# vm_mini_main3a.net
KiCad netlist of a schematic drawn in EAGLE
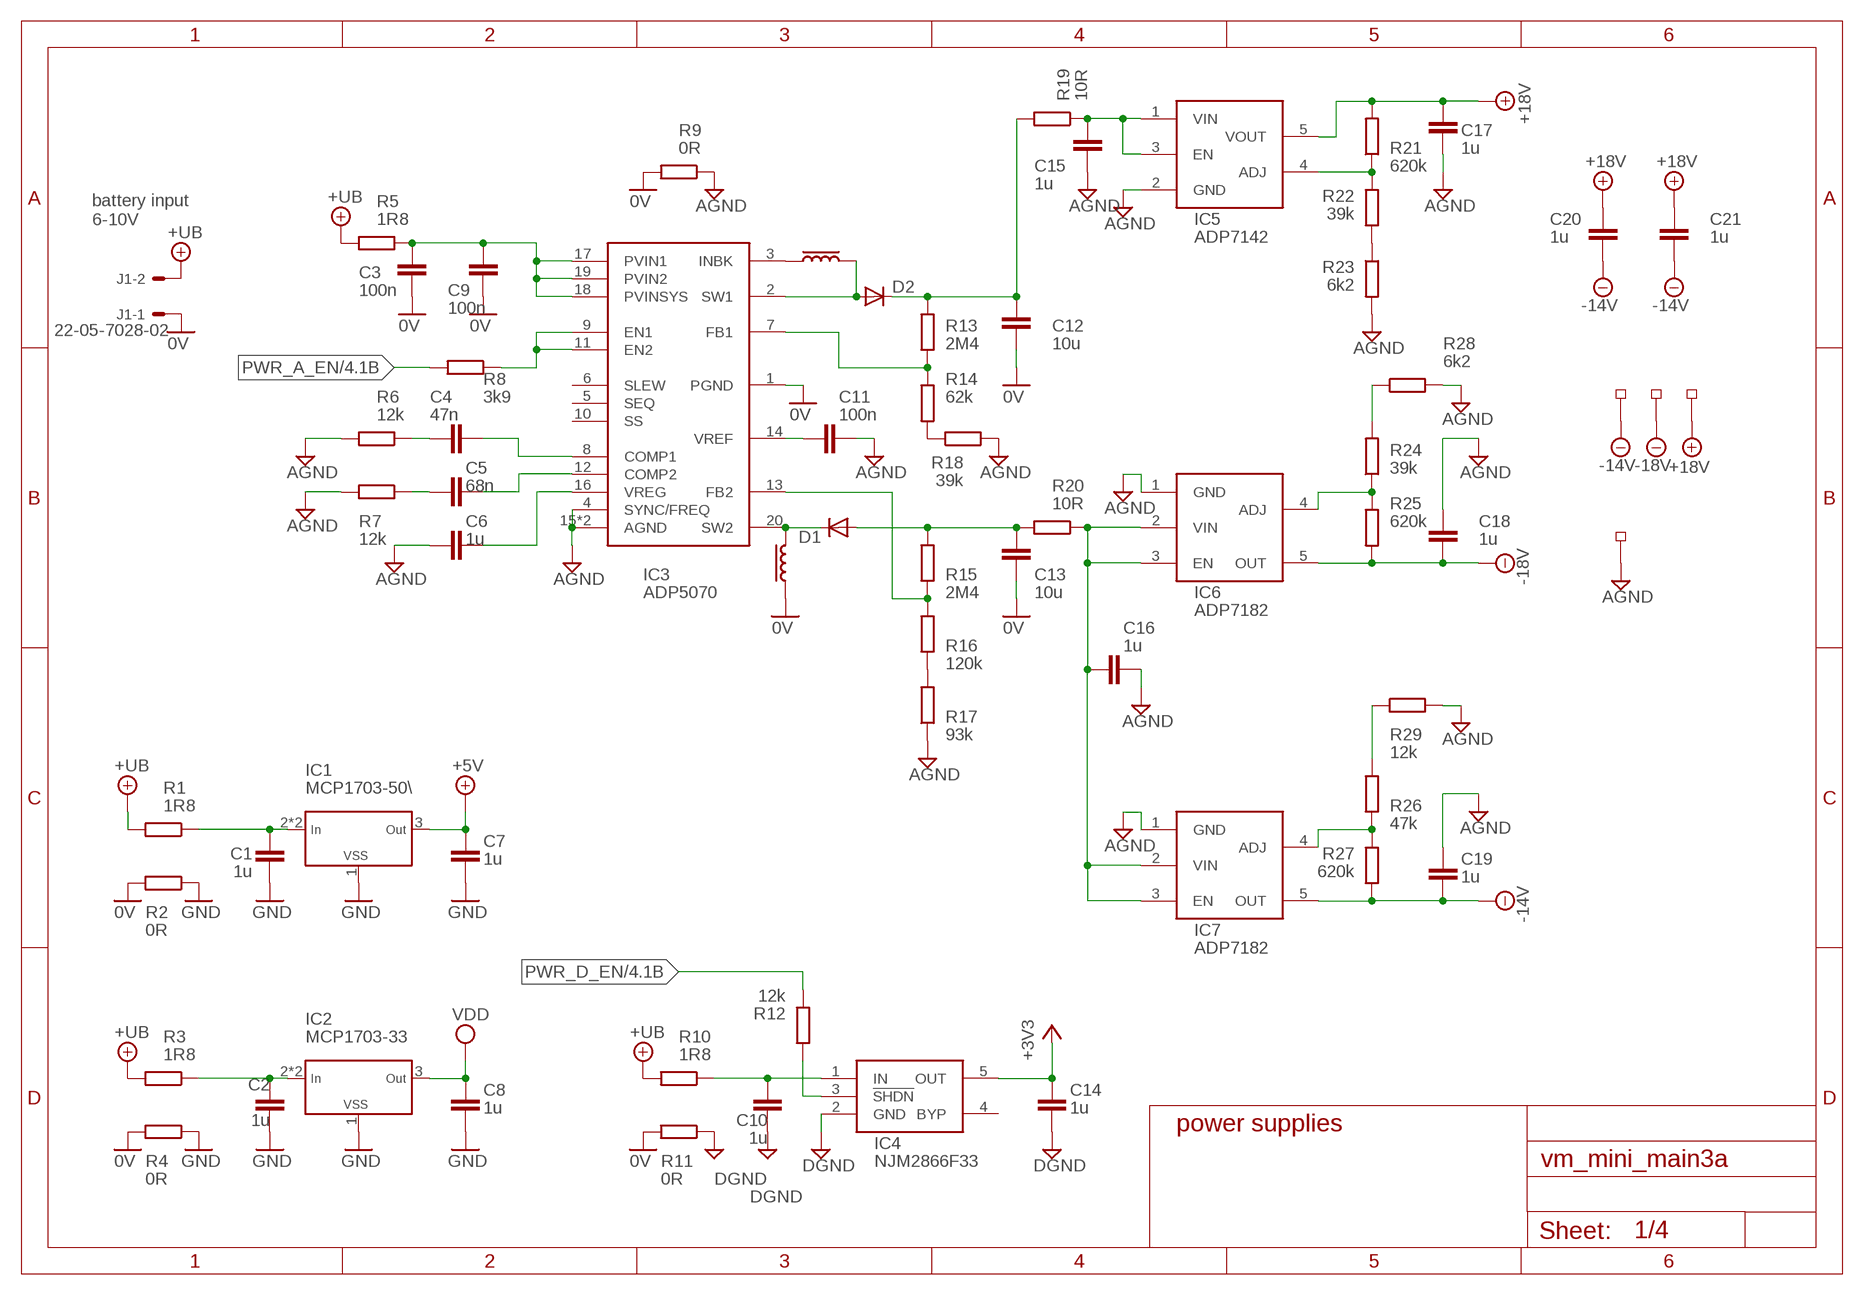
[diagram p0: schematic, sheet 1]
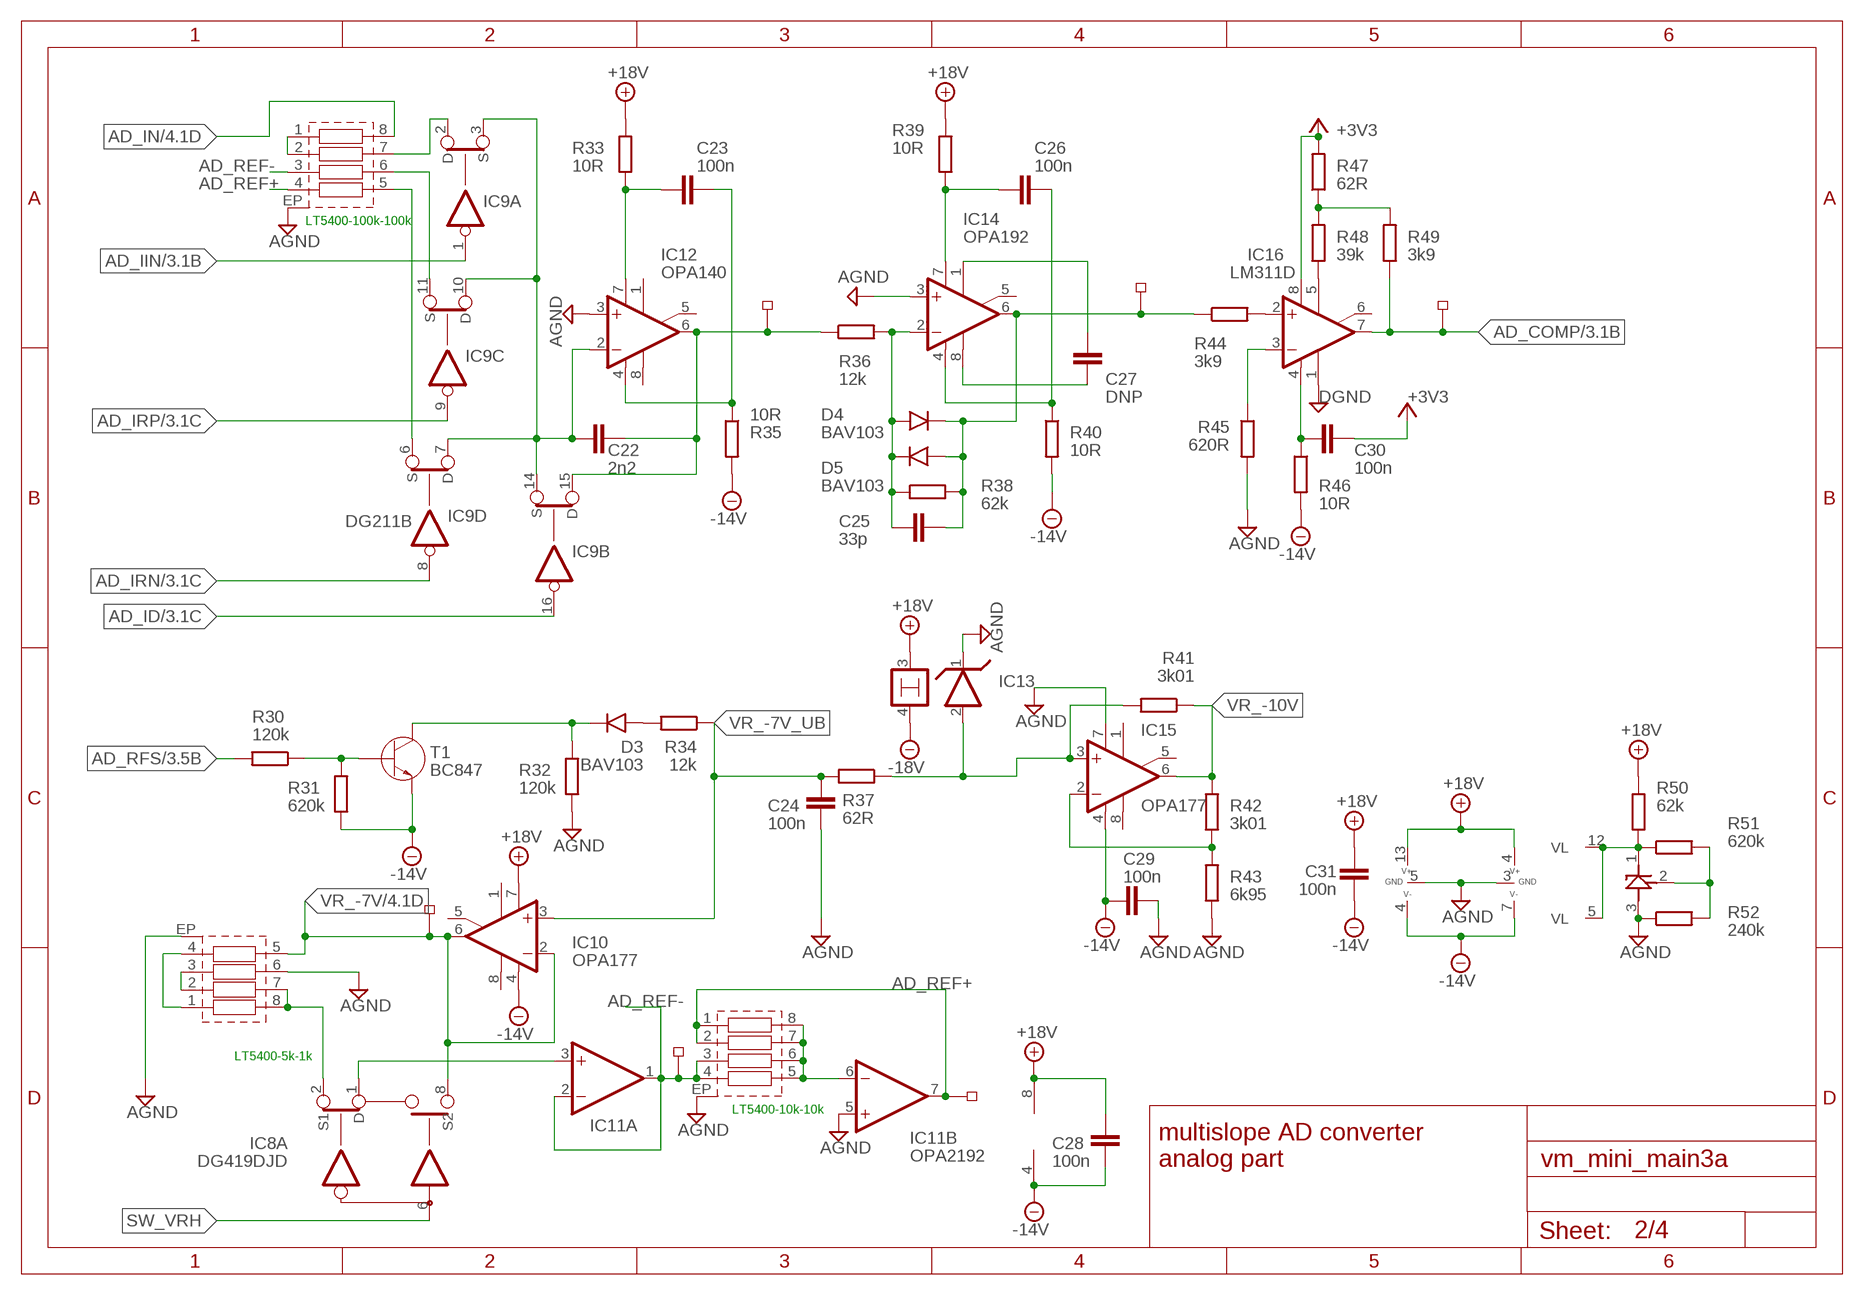
[diagram p1: schematic, sheet 2]
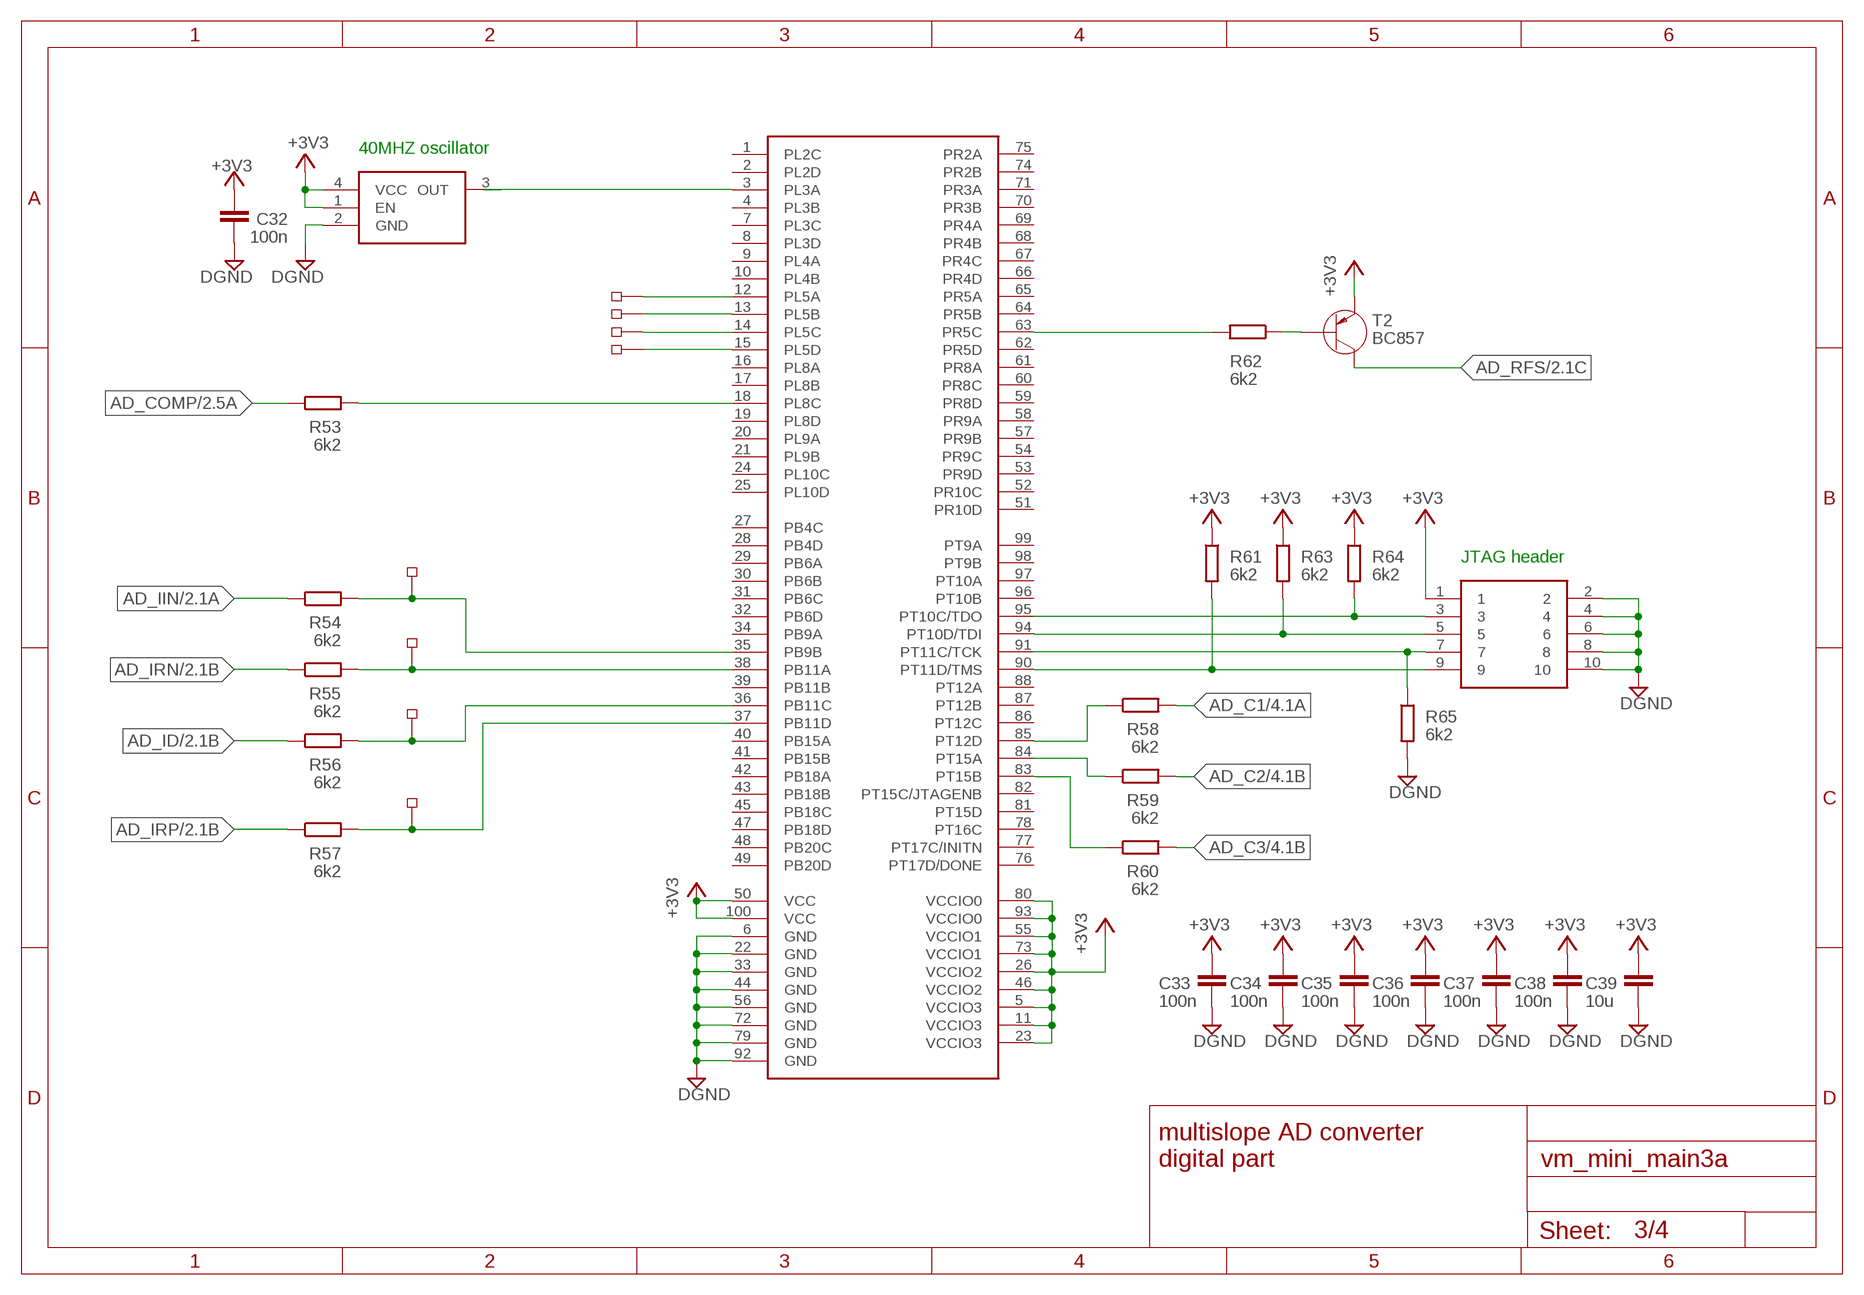
[diagram p2: schematic, sheet 3]
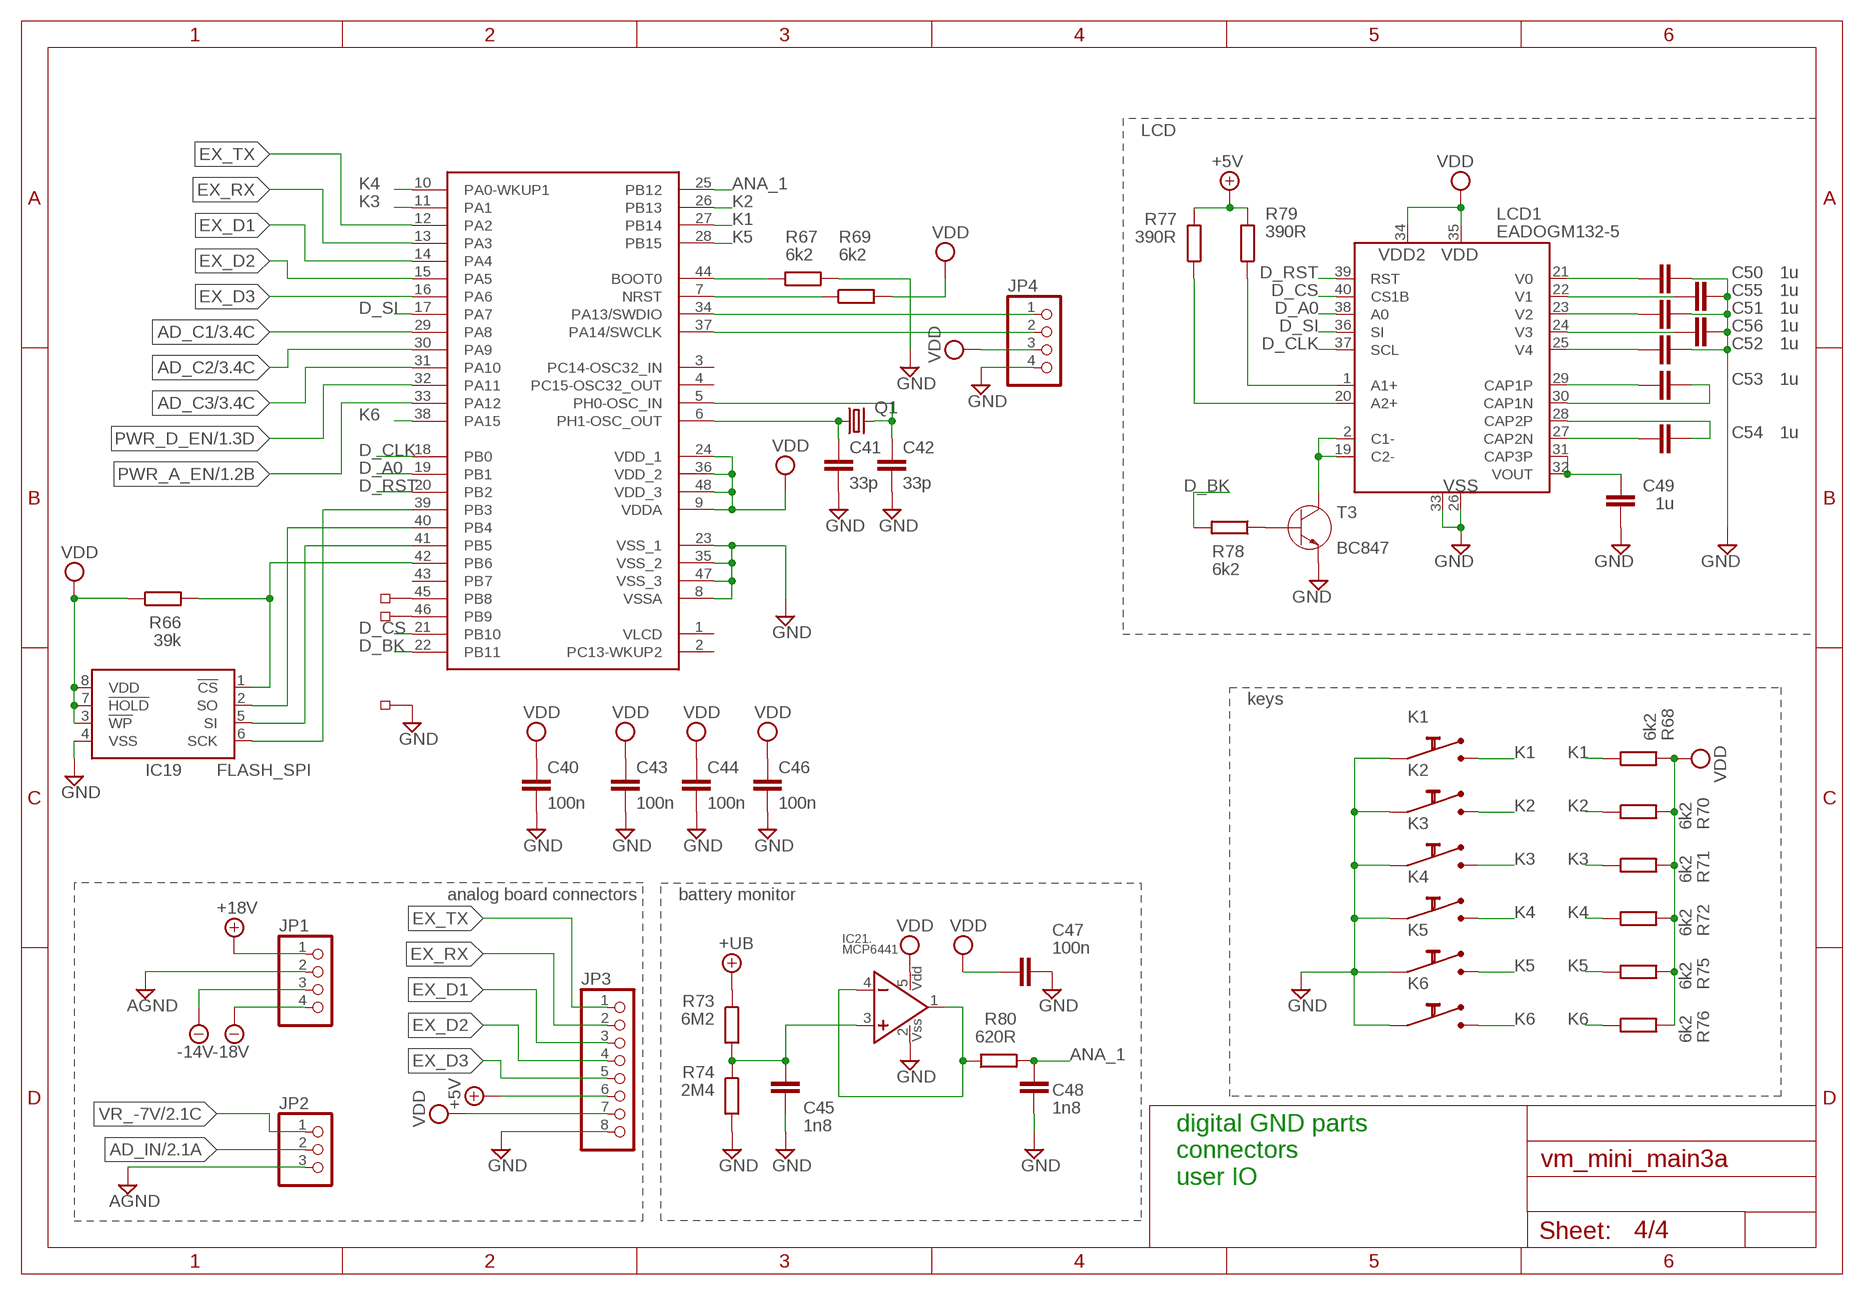
[diagram p3: schematic, sheet 4]

(export (version "E")
  (design (tool "Eeschema 10.0.6"))
  (components
    (comp (ref "C22")
      (value "2n2")
      (footprint "eagle-import:C150-054X183")
      (libsource (lib "eagle-import") (part "C-EU150-054X183"))
    )
    (comp (ref "C23")
      (value "100n")
      (footprint "eagle-import:R0805")
      (libsource (lib "eagle-import") (part "C_0806"))
    )
    (comp (ref "C24")
      (value "100n")
      (footprint "eagle-import:C050-035X075")
      (libsource (lib "eagle-import") (part "C-EU050-035X075"))
    )
    (comp (ref "C25")
      (value "33p")
      (footprint "eagle-import:R_MINIMELF")
      (libsource (lib "eagle-import") (part "CMM"))
    )
    (comp (ref "C26")
      (value "100n")
      (footprint "eagle-import:R0805")
      (libsource (lib "eagle-import") (part "C_0806"))
    )
    (comp (ref "C27")
      (value "DNP")
      (footprint "eagle-import:R_MINIMELF")
      (libsource (lib "eagle-import") (part "CMM"))
    )
    (comp (ref "C28")
      (value "100n")
      (footprint "eagle-import:R0805")
      (libsource (lib "eagle-import") (part "C_0806"))
    )
    (comp (ref "C29")
      (value "100n")
      (footprint "eagle-import:R0805")
      (libsource (lib "eagle-import") (part "C_0806"))
    )
    (comp (ref "C30")
      (value "100n")
      (footprint "eagle-import:R0805")
      (libsource (lib "eagle-import") (part "C_0806"))
    )
    (comp (ref "C31")
      (value "100n")
      (footprint "eagle-import:R0805")
      (libsource (lib "eagle-import") (part "C_0806"))
    )
    (comp (ref "D3")
      (value "BAV103")
      (footprint "eagle-import:SOD-80")
      (libsource (lib "eagle-import") (part "1N4148SOD"))
    )
    (comp (ref "D4")
      (value "BAV103")
      (footprint "eagle-import:SOD-80")
      (libsource (lib "eagle-import") (part "1N4148SOD"))
    )
    (comp (ref "D5")
      (value "BAV103")
      (footprint "eagle-import:SOD-80")
      (libsource (lib "eagle-import") (part "1N4148SOD"))
    )
    (comp (ref "IC8")
      (value "DG419DJD")
      (footprint "eagle-import:SO08")
      (libsource (lib "eagle-import") (part "DG419DJD"))
    )
    (comp (ref "IC9")
      (value "DG211B")
      (footprint "eagle-import:SO16")
      (libsource (lib "eagle-import") (part "DG211CJD"))
    )
    (comp (ref "IC10")
      (value "OPA177")
      (footprint "eagle-import:SO08")
      (libsource (lib "eagle-import") (part "TL071D"))
    )
    (comp (ref "IC11")
      (value "OPA2192")
      (footprint "eagle-import:SO08")
      (libsource (lib "eagle-import") (part "TL072D"))
    )
    (comp (ref "IC12")
      (value "OPA140")
      (footprint "eagle-import:SO08")
      (libsource (lib "eagle-import") (part "TL071D"))
    )
    (comp (ref "IC13")
      (value "LM399H")
      (footprint "eagle-import:TO39_4")
      (libsource (lib "eagle-import") (part "LM399H"))
    )
    (comp (ref "IC14")
      (value "OPA192")
      (footprint "eagle-import:SO08")
      (libsource (lib "eagle-import") (part "TL071D"))
    )
    (comp (ref "IC15")
      (value "OPA177")
      (footprint "eagle-import:SO08")
      (libsource (lib "eagle-import") (part "TL071D"))
    )
    (comp (ref "IC16")
      (value "LM311D")
      (footprint "eagle-import:SO08")
      (libsource (lib "eagle-import") (part "LM311D"))
    )
    (comp (ref "IC17")
      (value "TL431_SOT23")
      (footprint "eagle-import:SOT23")
      (libsource (lib "eagle-import") (part "TL431_SOT23"))
    )
    (comp (ref "R30")
      (value "120k")
      (footprint "eagle-import:R_MINIMELF")
      (libsource (lib "eagle-import") (part "RMMELF"))
    )
    (comp (ref "R31")
      (value "620k")
      (footprint "eagle-import:R_MINIMELF")
      (libsource (lib "eagle-import") (part "RMMELF"))
    )
    (comp (ref "R32")
      (value "120k")
      (footprint "eagle-import:R_MINIMELF")
      (libsource (lib "eagle-import") (part "RMMELF"))
    )
    (comp (ref "R33")
      (value "10R")
      (footprint "eagle-import:R_MINIMELF")
      (libsource (lib "eagle-import") (part "RMMELF"))
    )
    (comp (ref "R34")
      (value "12k")
      (footprint "eagle-import:R_MINIMELF")
      (libsource (lib "eagle-import") (part "RMMELF"))
    )
    (comp (ref "R35")
      (value "10R")
      (footprint "eagle-import:R_MINIMELF")
      (libsource (lib "eagle-import") (part "RMMELF"))
    )
    (comp (ref "R36")
      (value "12k")
      (footprint "eagle-import:R_MINIMELF")
      (libsource (lib "eagle-import") (part "RMMELF"))
    )
    (comp (ref "R37")
      (value "62R")
      (footprint "eagle-import:R_MINIMELF")
      (libsource (lib "eagle-import") (part "RMMELF"))
    )
    (comp (ref "R38")
      (value "62k")
      (footprint "eagle-import:R_MINIMELF")
      (libsource (lib "eagle-import") (part "RMMELF"))
    )
    (comp (ref "R39")
      (value "10R")
      (footprint "eagle-import:R_MINIMELF")
      (libsource (lib "eagle-import") (part "RMMELF"))
    )
    (comp (ref "R40")
      (value "10R")
      (footprint "eagle-import:R_MINIMELF")
      (libsource (lib "eagle-import") (part "RMMELF"))
    )
    (comp (ref "R41")
      (value "3k01")
      (footprint "eagle-import:R_TR191")
      (libsource (lib "eagle-import") (part "R191"))
    )
    (comp (ref "R42")
      (value "3k01")
      (footprint "eagle-import:R_TR191")
      (libsource (lib "eagle-import") (part "R191"))
    )
    (comp (ref "R43")
      (value "6k95")
      (footprint "eagle-import:R_TR191")
      (libsource (lib "eagle-import") (part "R191"))
    )
    (comp (ref "R44")
      (value "3k9")
      (footprint "eagle-import:R_MINIMELF")
      (libsource (lib "eagle-import") (part "RMMELF"))
    )
    (comp (ref "R45")
      (value "620R")
      (footprint "eagle-import:R_MINIMELF")
      (libsource (lib "eagle-import") (part "RMMELF"))
    )
    (comp (ref "R46")
      (value "10R")
      (footprint "eagle-import:R_MINIMELF")
      (libsource (lib "eagle-import") (part "RMMELF"))
    )
    (comp (ref "R47")
      (value "62R")
      (footprint "eagle-import:R_MINIMELF")
      (libsource (lib "eagle-import") (part "RMMELF"))
    )
    (comp (ref "R48")
      (value "39k")
      (footprint "eagle-import:R_MINIMELF")
      (libsource (lib "eagle-import") (part "RMMELF"))
    )
    (comp (ref "R49")
      (value "3k9")
      (footprint "eagle-import:R_MINIMELF")
      (libsource (lib "eagle-import") (part "RMMELF"))
    )
    (comp (ref "R50")
      (value "62k")
      (footprint "eagle-import:R_MINIMELF")
      (libsource (lib "eagle-import") (part "RMMELF"))
    )
    (comp (ref "R51")
      (value "620k")
      (footprint "eagle-import:R_MINIMELF")
      (libsource (lib "eagle-import") (part "RMMELF"))
    )
    (comp (ref "R52")
      (value "240k")
      (footprint "eagle-import:R_MINIMELF")
      (libsource (lib "eagle-import") (part "RMMELF"))
    )
    (comp (ref "RN1")
      (value "LT5400-5k-1k")
      (footprint "eagle-import:MSOP8-EP")
      (libsource (lib "eagle-import") (part "LT5400"))
    )
    (comp (ref "RN2")
      (value "LT5400-100k-100k")
      (footprint "eagle-import:MSOP8-EP")
      (libsource (lib "eagle-import") (part "LT5400"))
    )
    (comp (ref "RN3")
      (value "LT5400-10k+10k")
      (footprint "eagle-import:MSOP8-EP")
      (libsource (lib "eagle-import") (part "LT5400"))
    )
    (comp (ref "T1")
      (value "BC847")
      (footprint "eagle-import:SOT23")
      (libsource (lib "eagle-import") (part "BC847"))
    )
    (comp (ref "TP5")
      (value "TEST_PADSMD_35X2")
      (footprint "eagle-import:TP_SMD_35X2")
      (libsource (lib "eagle-import") (part "TEST_PADSMD_35X2"))
    )
    (comp (ref "TP6")
      (value "TEST_PADSMD_35X2")
      (footprint "eagle-import:TP_SMD_35X2")
      (libsource (lib "eagle-import") (part "TEST_PADSMD_35X2"))
    )
    (comp (ref "TP7")
      (value "TEST_PADSMD_35X2")
      (footprint "eagle-import:TP_SMD_35X2")
      (libsource (lib "eagle-import") (part "TEST_PADSMD_35X2"))
    )
    (comp (ref "TP8")
      (value "TEST_PADSMD_35X2")
      (footprint "eagle-import:TP_SMD_35X2")
      (libsource (lib "eagle-import") (part "TEST_PADSMD_35X2"))
    )
    (comp (ref "TP9")
      (value "TEST_PADSMD_35X2")
      (footprint "eagle-import:TP_SMD_35X2")
      (libsource (lib "eagle-import") (part "TEST_PADSMD_35X2"))
    )
    (comp (ref "TP21")
      (value "TEST_PADSMD_35X2")
      (footprint "eagle-import:TP_SMD_35X2")
      (libsource (lib "eagle-import") (part "TEST_PADSMD_35X2"))
    )
    (comp (ref "C40")
      (value "100n")
      (footprint "eagle-import:R0805")
      (libsource (lib "eagle-import") (part "C_0806"))
    )
    (comp (ref "C41")
      (value "33p")
      (footprint "eagle-import:R0805")
      (libsource (lib "eagle-import") (part "C_0806"))
    )
    (comp (ref "C42")
      (value "33p")
      (footprint "eagle-import:R0805")
      (libsource (lib "eagle-import") (part "C_0806"))
    )
    (comp (ref "C43")
      (value "100n")
      (footprint "eagle-import:R0805")
      (libsource (lib "eagle-import") (part "C_0806"))
    )
    (comp (ref "C44")
      (value "100n")
      (footprint "eagle-import:R0805")
      (libsource (lib "eagle-import") (part "C_0806"))
    )
    (comp (ref "C45")
      (value "1n8")
      (footprint "eagle-import:R_MINIMELF")
      (libsource (lib "eagle-import") (part "CMM"))
    )
    (comp (ref "C46")
      (value "100n")
      (footprint "eagle-import:R0805")
      (libsource (lib "eagle-import") (part "C_0806"))
    )
    (comp (ref "C47")
      (value "100n")
      (footprint "eagle-import:R0805")
      (libsource (lib "eagle-import") (part "C_0806"))
    )
    (comp (ref "C48")
      (value "1n8")
      (footprint "eagle-import:R_MINIMELF")
      (libsource (lib "eagle-import") (part "CMM"))
    )
    (comp (ref "C49")
      (value "1u")
      (footprint "eagle-import:R0805")
      (libsource (lib "eagle-import") (part "C_0806"))
    )
    (comp (ref "C50")
      (value "1u")
      (footprint "eagle-import:R0805")
      (libsource (lib "eagle-import") (part "C_0806"))
    )
    (comp (ref "C51")
      (value "1u")
      (footprint "eagle-import:R0805")
      (libsource (lib "eagle-import") (part "C_0806"))
    )
    (comp (ref "C52")
      (value "1u")
      (footprint "eagle-import:R0805")
      (libsource (lib "eagle-import") (part "C_0806"))
    )
    (comp (ref "C53")
      (value "1u")
      (footprint "eagle-import:R0805")
      (libsource (lib "eagle-import") (part "C_0806"))
    )
    (comp (ref "C54")
      (value "1u")
      (footprint "eagle-import:R0805")
      (libsource (lib "eagle-import") (part "C_0806"))
    )
    (comp (ref "C55")
      (value "1u")
      (footprint "eagle-import:R0805")
      (libsource (lib "eagle-import") (part "C_0806"))
    )
    (comp (ref "C56")
      (value "1u")
      (footprint "eagle-import:R0805")
      (libsource (lib "eagle-import") (part "C_0806"))
    )
    (comp (ref "IC19")
      (value "FLASH_SPI")
      (footprint "eagle-import:SO-08")
      (libsource (lib "eagle-import") (part "EEPROM_SPI-SOIC"))
    )
    (comp (ref "IC20")
      (value "STM32L152XC_LQFP48")
      (footprint "eagle-import:LQFP48")
      (libsource (lib "eagle-import") (part "STM32L152XC_LQFP48"))
    )
    (comp (ref "IC21")
      (value "MCP6441")
      (footprint "eagle-import:SOT23-5L")
      (libsource (lib "eagle-import") (part "MCP6021"))
    )
    (comp (ref "JP1")
      (value "PINHD-1X04_2.54")
      (footprint "eagle-import:1X04")
      (libsource (lib "eagle-import") (part "PINHD-1X04_2.54"))
    )
    (comp (ref "JP2")
      (value "PINHD-1X03_2.54")
      (footprint "eagle-import:1X03")
      (libsource (lib "eagle-import") (part "PINHD-1X03_2.54"))
    )
    (comp (ref "JP3")
      (value "PINHD-1X08_2.54")
      (footprint "eagle-import:1X08")
      (libsource (lib "eagle-import") (part "PINHD-1X08_2.54"))
    )
    (comp (ref "JP4")
      (value "PINHD-1X04_2.54-90°")
      (footprint "eagle-import:1X04_90")
      (libsource (lib "eagle-import") (part "PINHD-1X04_2.54-90°"))
    )
    (comp (ref "K1")
      (value "SWITCH_MINI6450")
      (footprint "eagle-import:SWITCH_6450")
      (libsource (lib "eagle-import") (part "SWITCH_MINI6450"))
    )
    (comp (ref "K2")
      (value "SWITCH_MINI6450")
      (footprint "eagle-import:SWITCH_6450")
      (libsource (lib "eagle-import") (part "SWITCH_MINI6450"))
    )
    (comp (ref "K3")
      (value "SWITCH_MINI6450")
      (footprint "eagle-import:SWITCH_6450")
      (libsource (lib "eagle-import") (part "SWITCH_MINI6450"))
    )
    (comp (ref "K4")
      (value "SWITCH_MINI6450")
      (footprint "eagle-import:SWITCH_6450")
      (libsource (lib "eagle-import") (part "SWITCH_MINI6450"))
    )
    (comp (ref "K5")
      (value "SWITCH_MINI6450")
      (footprint "eagle-import:SWITCH_6450")
      (libsource (lib "eagle-import") (part "SWITCH_MINI6450"))
    )
    (comp (ref "K6")
      (value "SWITCH_MINI6450")
      (footprint "eagle-import:SWITCH_6450")
      (libsource (lib "eagle-import") (part "SWITCH_MINI6450"))
    )
    (comp (ref "LCD1")
      (value "EADOGM132-5")
      (footprint "eagle-import:EADOGM")
      (libsource (lib "eagle-import") (part "EADOGM132-5"))
    )
    (comp (ref "Q1")
      (value "CRYSTALHC49UP")
      (footprint "eagle-import:HC49UP")
      (libsource (lib "eagle-import") (part "CRYSTALHC49UP"))
    )
    (comp (ref "R66")
      (value "39k")
      (footprint "eagle-import:R_MINIMELF")
      (libsource (lib "eagle-import") (part "RMMELF"))
    )
    (comp (ref "R67")
      (value "6k2")
      (footprint "eagle-import:R_MINIMELF")
      (libsource (lib "eagle-import") (part "RMMELF"))
    )
    (comp (ref "R68")
      (value "6k2")
      (footprint "eagle-import:R_MINIMELF")
      (libsource (lib "eagle-import") (part "RMMELF"))
    )
    (comp (ref "R69")
      (value "6k2")
      (footprint "eagle-import:R_MINIMELF")
      (libsource (lib "eagle-import") (part "RMMELF"))
    )
    (comp (ref "R70")
      (value "6k2")
      (footprint "eagle-import:R_MINIMELF")
      (libsource (lib "eagle-import") (part "RMMELF"))
    )
    (comp (ref "R71")
      (value "6k2")
      (footprint "eagle-import:R_MINIMELF")
      (libsource (lib "eagle-import") (part "RMMELF"))
    )
    (comp (ref "R72")
      (value "6k2")
      (footprint "eagle-import:R_MINIMELF")
      (libsource (lib "eagle-import") (part "RMMELF"))
    )
    (comp (ref "R73")
      (value "6M2")
      (footprint "eagle-import:R_MINIMELF")
      (libsource (lib "eagle-import") (part "RMMELF"))
    )
    (comp (ref "R74")
      (value "2M4")
      (footprint "eagle-import:R_MINIMELF")
      (libsource (lib "eagle-import") (part "RMMELF"))
    )
    (comp (ref "R75")
      (value "6k2")
      (footprint "eagle-import:R_MINIMELF")
      (libsource (lib "eagle-import") (part "RMMELF"))
    )
    (comp (ref "R76")
      (value "6k2")
      (footprint "eagle-import:R_MINIMELF")
      (libsource (lib "eagle-import") (part "RMMELF"))
    )
    (comp (ref "R77")
      (value "390R")
      (footprint "eagle-import:R_MINIMELF")
      (libsource (lib "eagle-import") (part "RMMELF"))
    )
    (comp (ref "R78")
      (value "6k2")
      (footprint "eagle-import:R_MINIMELF")
      (libsource (lib "eagle-import") (part "RMMELF"))
    )
    (comp (ref "R79")
      (value "390R")
      (footprint "eagle-import:R_MINIMELF")
      (libsource (lib "eagle-import") (part "RMMELF"))
    )
    (comp (ref "R80")
      (value "620R")
      (footprint "eagle-import:R_MINIMELF")
      (libsource (lib "eagle-import") (part "RMMELF"))
    )
    (comp (ref "T3")
      (value "BC847")
      (footprint "eagle-import:SOT23")
      (libsource (lib "eagle-import") (part "BC847"))
    )
    (comp (ref "TP18")
      (value "TEST_PADSMD_35X2")
      (footprint "eagle-import:TP_SMD_35X2")
      (libsource (lib "eagle-import") (part "TEST_PADSMD_35X2"))
    )
    (comp (ref "TP19")
      (value "TEST_PADSMD_35X2")
      (footprint "eagle-import:TP_SMD_35X2")
      (libsource (lib "eagle-import") (part "TEST_PADSMD_35X2"))
    )
    (comp (ref "TP20")
      (value "TEST_PADSMD_35X2")
      (footprint "eagle-import:TP_SMD_35X2")
      (libsource (lib "eagle-import") (part "TEST_PADSMD_35X2"))
    )
    (comp (ref "C32")
      (value "100n")
      (footprint "eagle-import:R0805")
      (libsource (lib "eagle-import") (part "C_0806"))
    )
    (comp (ref "C33")
      (value "100n")
      (footprint "eagle-import:R0805")
      (libsource (lib "eagle-import") (part "C_0806"))
    )
    (comp (ref "C34")
      (value "100n")
      (footprint "eagle-import:R0805")
      (libsource (lib "eagle-import") (part "C_0806"))
    )
    (comp (ref "C35")
      (value "100n")
      (footprint "eagle-import:R0805")
      (libsource (lib "eagle-import") (part "C_0806"))
    )
    (comp (ref "C36")
      (value "100n")
      (footprint "eagle-import:R0805")
      (libsource (lib "eagle-import") (part "C_0806"))
    )
    (comp (ref "C37")
      (value "100n")
      (footprint "eagle-import:R0805")
      (libsource (lib "eagle-import") (part "C_0806"))
    )
    (comp (ref "C38")
      (value "100n")
      (footprint "eagle-import:R0805")
      (libsource (lib "eagle-import") (part "C_0806"))
    )
    (comp (ref "C39")
      (value "10u")
      (footprint "eagle-import:R0805")
      (libsource (lib "eagle-import") (part "C_0806"))
    )
    (comp (ref "CON1")
      (value "IDC_10_2MM")
      (footprint "eagle-import:IDC_20_10P")
      (libsource (lib "eagle-import") (part "IDC_10_2MM"))
    )
    (comp (ref "IC18")
      (value "MACHXO2-1200-TQ100T100")
      (footprint "eagle-import:TQFP100")
      (libsource (lib "eagle-import") (part "MACHXO2-1200-TQ100T100"))
    )
    (comp (ref "OSC1")
      (value "OSC3225")
      (footprint "eagle-import:OSC_3225")
      (libsource (lib "eagle-import") (part "OSC3225"))
    )
    (comp (ref "R53")
      (value "6k2")
      (footprint "eagle-import:R_MINIMELF")
      (libsource (lib "eagle-import") (part "RMMELF"))
    )
    (comp (ref "R54")
      (value "6k2")
      (footprint "eagle-import:R_MINIMELF")
      (libsource (lib "eagle-import") (part "RMMELF"))
    )
    (comp (ref "R55")
      (value "6k2")
      (footprint "eagle-import:R_MINIMELF")
      (libsource (lib "eagle-import") (part "RMMELF"))
    )
    (comp (ref "R56")
      (value "6k2")
      (footprint "eagle-import:R_MINIMELF")
      (libsource (lib "eagle-import") (part "RMMELF"))
    )
    (comp (ref "R57")
      (value "6k2")
      (footprint "eagle-import:R_MINIMELF")
      (libsource (lib "eagle-import") (part "RMMELF"))
    )
    (comp (ref "R58")
      (value "6k2")
      (footprint "eagle-import:R_MINIMELF")
      (libsource (lib "eagle-import") (part "RMMELF"))
    )
    (comp (ref "R59")
      (value "6k2")
      (footprint "eagle-import:R_MINIMELF")
      (libsource (lib "eagle-import") (part "RMMELF"))
    )
    (comp (ref "R60")
      (value "6k2")
      (footprint "eagle-import:R_MINIMELF")
      (libsource (lib "eagle-import") (part "RMMELF"))
    )
    (comp (ref "R61")
      (value "6k2")
      (footprint "eagle-import:R_MINIMELF")
      (libsource (lib "eagle-import") (part "RMMELF"))
    )
    (comp (ref "R62")
      (value "6k2")
      (footprint "eagle-import:R_MINIMELF")
      (libsource (lib "eagle-import") (part "RMMELF"))
    )
    (comp (ref "R63")
      (value "6k2")
      (footprint "eagle-import:R_MINIMELF")
      (libsource (lib "eagle-import") (part "RMMELF"))
    )
    (comp (ref "R64")
      (value "6k2")
      (footprint "eagle-import:R_MINIMELF")
      (libsource (lib "eagle-import") (part "RMMELF"))
    )
    (comp (ref "R65")
      (value "6k2")
      (footprint "eagle-import:R_MINIMELF")
      (libsource (lib "eagle-import") (part "RMMELF"))
    )
    (comp (ref "T2")
      (value "BC857")
      (footprint "eagle-import:SOT23")
      (libsource (lib "eagle-import") (part "BC857"))
    )
    (comp (ref "TP10")
      (value "TEST_PADSMD_35X2")
      (footprint "eagle-import:TP_SMD_35X2")
      (libsource (lib "eagle-import") (part "TEST_PADSMD_35X2"))
    )
    (comp (ref "TP11")
      (value "TEST_PADSMD_35X2")
      (footprint "eagle-import:TP_SMD_35X2")
      (libsource (lib "eagle-import") (part "TEST_PADSMD_35X2"))
    )
    (comp (ref "TP12")
      (value "TEST_PADSMD_35X2")
      (footprint "eagle-import:TP_SMD_35X2")
      (libsource (lib "eagle-import") (part "TEST_PADSMD_35X2"))
    )
    (comp (ref "TP13")
      (value "TEST_PADSMD_35X2")
      (footprint "eagle-import:TP_SMD_35X2")
      (libsource (lib "eagle-import") (part "TEST_PADSMD_35X2"))
    )
    (comp (ref "TP14")
      (value "TEST_PADSMD_35X2")
      (footprint "eagle-import:TP_SMD_35X2")
      (libsource (lib "eagle-import") (part "TEST_PADSMD_35X2"))
    )
    (comp (ref "TP15")
      (value "TEST_PADSMD_35X2")
      (footprint "eagle-import:TP_SMD_35X2")
      (libsource (lib "eagle-import") (part "TEST_PADSMD_35X2"))
    )
    (comp (ref "TP16")
      (value "TEST_PADSMD_35X2")
      (footprint "eagle-import:TP_SMD_35X2")
      (libsource (lib "eagle-import") (part "TEST_PADSMD_35X2"))
    )
    (comp (ref "TP17")
      (value "TEST_PADSMD_35X2")
      (footprint "eagle-import:TP_SMD_35X2")
      (libsource (lib "eagle-import") (part "TEST_PADSMD_35X2"))
    )
    (comp (ref "C1")
      (value "1u")
      (footprint "eagle-import:R0805")
      (libsource (lib "eagle-import") (part "C_0806"))
    )
    (comp (ref "C2")
      (value "1u")
      (footprint "eagle-import:R0805")
      (libsource (lib "eagle-import") (part "C_0806"))
    )
    (comp (ref "C3")
      (value "100n")
      (footprint "eagle-import:R0805")
      (libsource (lib "eagle-import") (part "C_0806"))
    )
    (comp (ref "C4")
      (value "47n")
      (footprint "eagle-import:R0805")
      (libsource (lib "eagle-import") (part "C_0806"))
    )
    (comp (ref "C5")
      (value "68n")
      (footprint "eagle-import:R0805")
      (libsource (lib "eagle-import") (part "C_0806"))
    )
    (comp (ref "C6")
      (value "1u")
      (footprint "eagle-import:R0805")
      (libsource (lib "eagle-import") (part "C_0806"))
    )
    (comp (ref "C7")
      (value "1u")
      (footprint "eagle-import:R0805")
      (libsource (lib "eagle-import") (part "C_0806"))
    )
    (comp (ref "C8")
      (value "1u")
      (footprint "eagle-import:R0805")
      (libsource (lib "eagle-import") (part "C_0806"))
    )
    (comp (ref "C9")
      (value "100n")
      (footprint "eagle-import:R0805")
      (libsource (lib "eagle-import") (part "C_0806"))
    )
    (comp (ref "C10")
      (value "1u")
      (footprint "eagle-import:R0805")
      (libsource (lib "eagle-import") (part "C_0806"))
    )
    (comp (ref "C11")
      (value "100n")
      (footprint "eagle-import:R0805")
      (libsource (lib "eagle-import") (part "C_0806"))
    )
    (comp (ref "C12")
      (value "10u")
      (footprint "eagle-import:R0805")
      (libsource (lib "eagle-import") (part "C_0806"))
    )
    (comp (ref "C13")
      (value "10u")
      (footprint "eagle-import:R0805")
      (libsource (lib "eagle-import") (part "C_0806"))
    )
    (comp (ref "C14")
      (value "1u")
      (footprint "eagle-import:R0805")
      (libsource (lib "eagle-import") (part "C_0806"))
    )
    (comp (ref "C15")
      (value "1u")
      (footprint "eagle-import:R0805")
      (libsource (lib "eagle-import") (part "C_0806"))
    )
    (comp (ref "C16")
      (value "1u")
      (footprint "eagle-import:R0805")
      (libsource (lib "eagle-import") (part "C_0806"))
    )
    (comp (ref "C17")
      (value "1u")
      (footprint "eagle-import:R0805")
      (libsource (lib "eagle-import") (part "C_0806"))
    )
    (comp (ref "C18")
      (value "1u")
      (footprint "eagle-import:R0805")
      (libsource (lib "eagle-import") (part "C_0806"))
    )
    (comp (ref "C19")
      (value "1u")
      (footprint "eagle-import:R0805")
      (libsource (lib "eagle-import") (part "C_0806"))
    )
    (comp (ref "C20")
      (value "1u")
      (footprint "eagle-import:R0805")
      (libsource (lib "eagle-import") (part "C_0806"))
    )
    (comp (ref "C21")
      (value "1u")
      (footprint "eagle-import:R0805")
      (libsource (lib "eagle-import") (part "C_0806"))
    )
    (comp (ref "D1")
      (value "DIODE-MINIMELF")
      (footprint "eagle-import:MINIMELF")
      (libsource (lib "eagle-import") (part "DIODE-MINIMELF"))
    )
    (comp (ref "D2")
      (value "DIODE-MINIMELF")
      (footprint "eagle-import:MINIMELF")
      (libsource (lib "eagle-import") (part "DIODE-MINIMELF"))
    )
    (comp (ref "IC1")
      (value "MCP1703-50\\")
      (footprint "eagle-import:SOT89")
      (libsource (lib "eagle-import") (part "MCP1702-SOT89"))
    )
    (comp (ref "IC2")
      (value "MCP1703-33")
      (footprint "eagle-import:SOT89")
      (libsource (lib "eagle-import") (part "MCP1702-SOT89"))
    )
    (comp (ref "IC3")
      (value "ADP5070")
      (footprint "eagle-import:TSSOP20-EP")
      (libsource (lib "eagle-import") (part "ADP5070"))
    )
    (comp (ref "IC4")
      (value "NJM2866F33")
      (footprint "eagle-import:SOT23-5")
      (libsource (lib "eagle-import") (part "TC1015"))
    )
    (comp (ref "IC5")
      (value "ADP7142")
      (footprint "eagle-import:SOT23-5L")
      (libsource (lib "eagle-import") (part "ADP7142"))
    )
    (comp (ref "IC6")
      (value "ADP7182")
      (footprint "eagle-import:SOT23-5L")
      (libsource (lib "eagle-import") (part "ADP7182"))
    )
    (comp (ref "IC7")
      (value "ADP7182")
      (footprint "eagle-import:SOT23-5L")
      (libsource (lib "eagle-import") (part "ADP7182"))
    )
    (comp (ref "J1")
      (value "22-05-7028-02")
      (footprint "eagle-import:7395-02")
      (libsource (lib "eagle-import") (part "22-?-0205-7028"))
    )
    (comp (ref "L1")
      (value "INDUCTORBOURNS_SRP7030")
      (footprint "eagle-import:BOURNS_SRP7030")
      (libsource (lib "eagle-import") (part "INDUCTORBOURNS_SRP7030"))
    )
    (comp (ref "L2")
      (value "INDUCTORBOURNS_SRP7030")
      (footprint "eagle-import:BOURNS_SRP7030")
      (libsource (lib "eagle-import") (part "INDUCTORBOURNS_SRP7030"))
    )
    (comp (ref "R1")
      (value "1R8")
      (footprint "eagle-import:R_MINIMELF")
      (libsource (lib "eagle-import") (part "RMMELF"))
    )
    (comp (ref "R2")
      (value "0R")
      (footprint "eagle-import:R_MINIMELF")
      (libsource (lib "eagle-import") (part "RMMELF"))
    )
    (comp (ref "R3")
      (value "1R8")
      (footprint "eagle-import:R_MINIMELF")
      (libsource (lib "eagle-import") (part "RMMELF"))
    )
    (comp (ref "R4")
      (value "0R")
      (footprint "eagle-import:R_MINIMELF")
      (libsource (lib "eagle-import") (part "RMMELF"))
    )
    (comp (ref "R5")
      (value "1R8")
      (footprint "eagle-import:R_MINIMELF")
      (libsource (lib "eagle-import") (part "RMMELF"))
    )
    (comp (ref "R6")
      (value "12k")
      (footprint "eagle-import:R_MINIMELF")
      (libsource (lib "eagle-import") (part "RMMELF"))
    )
    (comp (ref "R7")
      (value "12k")
      (footprint "eagle-import:R_MINIMELF")
      (libsource (lib "eagle-import") (part "RMMELF"))
    )
    (comp (ref "R8")
      (value "3k9")
      (footprint "eagle-import:R_MINIMELF")
      (libsource (lib "eagle-import") (part "RMMELF"))
    )
    (comp (ref "R9")
      (value "0R")
      (footprint "eagle-import:R_MINIMELF")
      (libsource (lib "eagle-import") (part "RMMELF"))
    )
    (comp (ref "R10")
      (value "1R8")
      (footprint "eagle-import:R_MINIMELF")
      (libsource (lib "eagle-import") (part "RMMELF"))
    )
    (comp (ref "R11")
      (value "0R")
      (footprint "eagle-import:R_MINIMELF")
      (libsource (lib "eagle-import") (part "RMMELF"))
    )
    (comp (ref "R12")
      (value "12k")
      (footprint "eagle-import:R_MINIMELF")
      (libsource (lib "eagle-import") (part "RMMELF"))
    )
    (comp (ref "R13")
      (value "2M4")
      (footprint "eagle-import:R_MINIMELF")
      (libsource (lib "eagle-import") (part "RMMELF"))
    )
    (comp (ref "R14")
      (value "62k")
      (footprint "eagle-import:R_MINIMELF")
      (libsource (lib "eagle-import") (part "RMMELF"))
    )
    (comp (ref "R15")
      (value "2M4")
      (footprint "eagle-import:R_MINIMELF")
      (libsource (lib "eagle-import") (part "RMMELF"))
    )
    (comp (ref "R16")
      (value "120k")
      (footprint "eagle-import:R_MINIMELF")
      (libsource (lib "eagle-import") (part "RMMELF"))
    )
    (comp (ref "R17")
      (value "93k")
      (footprint "eagle-import:R_MINIMELF")
      (libsource (lib "eagle-import") (part "RMMELF"))
    )
    (comp (ref "R18")
      (value "39k")
      (footprint "eagle-import:R_MINIMELF")
      (libsource (lib "eagle-import") (part "RMMELF"))
    )
    (comp (ref "R19")
      (value "10R")
      (footprint "eagle-import:R_MINIMELF")
      (libsource (lib "eagle-import") (part "RMMELF"))
    )
    (comp (ref "R20")
      (value "10R")
      (footprint "eagle-import:R_MINIMELF")
      (libsource (lib "eagle-import") (part "RMMELF"))
    )
    (comp (ref "R21")
      (value "620k")
      (footprint "eagle-import:R_MINIMELF")
      (libsource (lib "eagle-import") (part "RMMELF"))
    )
    (comp (ref "R22")
      (value "39k")
      (footprint "eagle-import:R_MINIMELF")
      (libsource (lib "eagle-import") (part "RMMELF"))
    )
    (comp (ref "R23")
      (value "6k2")
      (footprint "eagle-import:R_MINIMELF")
      (libsource (lib "eagle-import") (part "RMMELF"))
    )
    (comp (ref "R24")
      (value "39k")
      (footprint "eagle-import:R_MINIMELF")
      (libsource (lib "eagle-import") (part "RMMELF"))
    )
    (comp (ref "R25")
      (value "620k")
      (footprint "eagle-import:R_MINIMELF")
      (libsource (lib "eagle-import") (part "RMMELF"))
    )
    (comp (ref "R26")
      (value "47k")
      (footprint "eagle-import:R_MINIMELF")
      (libsource (lib "eagle-import") (part "RMMELF"))
    )
    (comp (ref "R27")
      (value "620k")
      (footprint "eagle-import:R_MINIMELF")
      (libsource (lib "eagle-import") (part "RMMELF"))
    )
    (comp (ref "R28")
      (value "6k2")
      (footprint "eagle-import:R_MINIMELF")
      (libsource (lib "eagle-import") (part "RMMELF"))
    )
    (comp (ref "R29")
      (value "12k")
      (footprint "eagle-import:R_MINIMELF")
      (libsource (lib "eagle-import") (part "RMMELF"))
    )
    (comp (ref "TP1")
      (value "TEST_PADSMD_35X2")
      (footprint "eagle-import:TP_SMD_35X2")
      (libsource (lib "eagle-import") (part "TEST_PADSMD_35X2"))
    )
    (comp (ref "TP2")
      (value "TEST_PADSMD_35X2")
      (footprint "eagle-import:TP_SMD_35X2")
      (libsource (lib "eagle-import") (part "TEST_PADSMD_35X2"))
    )
    (comp (ref "TP3")
      (value "TEST_PADSMD_35X2")
      (footprint "eagle-import:TP_SMD_35X2")
      (libsource (lib "eagle-import") (part "TEST_PADSMD_35X2"))
    )
    (comp (ref "TP4")
      (value "TEST_PADSMD_35X2")
      (footprint "eagle-import:TP_SMD_35X2")
      (libsource (lib "eagle-import") (part "TEST_PADSMD_35X2"))
    )
  )
  (nets
    (net (code "1") (name "+3V3") (class "Default")
      (node (ref "C14") (pin "2") (pinfunction "2_2") (pintype "passive"))
      (node (ref "C30") (pin "1") (pinfunction "1_1") (pintype "passive"))
      (node (ref "C32") (pin "2") (pinfunction "2_2") (pintype "passive"))
      (node (ref "C33") (pin "2") (pinfunction "2_2") (pintype "passive"))
      (node (ref "C34") (pin "2") (pinfunction "2_2") (pintype "passive"))
      (node (ref "C35") (pin "2") (pinfunction "2_2") (pintype "passive"))
      (node (ref "C36") (pin "2") (pinfunction "2_2") (pintype "passive"))
      (node (ref "C37") (pin "2") (pinfunction "2_2") (pintype "passive"))
      (node (ref "C38") (pin "2") (pinfunction "2_2") (pintype "passive"))
      (node (ref "C39") (pin "2") (pinfunction "2_2") (pintype "passive"))
      (node (ref "CON1") (pin "1") (pinfunction "1_1") (pintype "bidirectional"))
      (node (ref "IC16") (pin "8") (pinfunction "V+_8") (pintype "power_in"))
      (node (ref "IC18") (pin "100") (pinfunction "VCC_100") (pintype "bidirectional"))
      (node (ref "IC18") (pin "11") (pinfunction "VCCIO3_11") (pintype "bidirectional"))
      (node (ref "IC18") (pin "23") (pinfunction "VCCIO3_23") (pintype "bidirectional"))
      (node (ref "IC18") (pin "26") (pinfunction "VCCIO2_26") (pintype "bidirectional"))
      (node (ref "IC18") (pin "46") (pinfunction "VCCIO2_46") (pintype "bidirectional"))
      (node (ref "IC18") (pin "5") (pinfunction "VCCIO3_5") (pintype "bidirectional"))
      (node (ref "IC18") (pin "50") (pinfunction "VCC_50") (pintype "bidirectional"))
      (node (ref "IC18") (pin "55") (pinfunction "VCCIO1_55") (pintype "bidirectional"))
      (node (ref "IC18") (pin "73") (pinfunction "VCCIO1_73") (pintype "bidirectional"))
      (node (ref "IC18") (pin "80") (pinfunction "VCCIO0_80") (pintype "bidirectional"))
      (node (ref "IC18") (pin "93") (pinfunction "VCCIO0_93") (pintype "bidirectional"))
      (node (ref "IC4") (pin "5") (pinfunction "OUT_5") (pintype "bidirectional"))
      (node (ref "OSC1") (pin "1") (pinfunction "EN_1") (pintype "bidirectional"))
      (node (ref "OSC1") (pin "4") (pinfunction "VCC_4") (pintype "bidirectional"))
      (node (ref "R47") (pin "P$2") (pinfunction "2_P$2") (pintype "passive"))
      (node (ref "R61") (pin "P$1") (pinfunction "1_P$1") (pintype "passive"))
      (node (ref "R63") (pin "P$1") (pinfunction "1_P$1") (pintype "passive"))
      (node (ref "R64") (pin "P$1") (pinfunction "1_P$1") (pintype "passive"))
      (node (ref "T2") (pin "2") (pinfunction "C_2") (pintype "passive"))
    )
    (net (code "2") (name "+5V") (class "Default")
      (node (ref "C7") (pin "2") (pinfunction "2_2") (pintype "passive"))
      (node (ref "IC1") (pin "3") (pinfunction "OUT_3") (pintype "output"))
      (node (ref "JP3") (pin "6") (pinfunction "6_6") (pintype "passive"))
      (node (ref "R77") (pin "P$2") (pinfunction "2_P$2") (pintype "passive"))
      (node (ref "R79") (pin "P$2") (pinfunction "2_P$2") (pintype "passive"))
    )
    (net (code "3") (name "+18V") (class "Default")
      (node (ref "C17") (pin "1") (pinfunction "1_1") (pintype "passive"))
      (node (ref "C20") (pin "1") (pinfunction "1_1") (pintype "passive"))
      (node (ref "C21") (pin "1") (pinfunction "1_1") (pintype "passive"))
      (node (ref "C28") (pin "2") (pinfunction "2_2") (pintype "passive"))
      (node (ref "C31") (pin "2") (pinfunction "2_2") (pintype "passive"))
      (node (ref "IC10") (pin "7") (pinfunction "V+_7") (pintype "power_in"))
      (node (ref "IC11") (pin "8") (pinfunction "V+_8") (pintype "power_in"))
      (node (ref "IC13") (pin "3") (pinfunction "3_3") (pintype "input"))
      (node (ref "IC5") (pin "5") (pinfunction "VOUT_5") (pintype "bidirectional"))
      (node (ref "IC8") (pin "4") (pinfunction "V+_4") (pintype "power_in"))
      (node (ref "IC9") (pin "13") (pinfunction "V+_13") (pintype "power_in"))
      (node (ref "JP1") (pin "1") (pinfunction "1_1") (pintype "passive"))
      (node (ref "R21") (pin "P$2") (pinfunction "2_P$2") (pintype "passive"))
      (node (ref "R33") (pin "P$2") (pinfunction "2_P$2") (pintype "passive"))
      (node (ref "R39") (pin "P$2") (pinfunction "2_P$2") (pintype "passive"))
      (node (ref "R50") (pin "P$1") (pinfunction "1_P$1") (pintype "passive"))
      (node (ref "TP3") (pin "P$1") (pinfunction "P$1_P$1") (pintype "bidirectional"))
    )
    (net (code "4") (name "+UB") (class "Default")
      (node (ref "J1") (pin "2") (pinfunction "S_2") (pintype "passive"))
      (node (ref "R1") (pin "P$2") (pinfunction "2_P$2") (pintype "passive"))
      (node (ref "R10") (pin "P$2") (pinfunction "2_P$2") (pintype "passive"))
      (node (ref "R3") (pin "P$2") (pinfunction "2_P$2") (pintype "passive"))
      (node (ref "R5") (pin "P$2") (pinfunction "2_P$2") (pintype "passive"))
      (node (ref "R73") (pin "P$1") (pinfunction "1_P$1") (pintype "passive"))
    )
    (net (code "5") (name "-14V") (class "Default")
      (node (ref "C19") (pin "2") (pinfunction "2_2") (pintype "passive"))
      (node (ref "C20") (pin "2") (pinfunction "2_2") (pintype "passive"))
      (node (ref "C21") (pin "2") (pinfunction "2_2") (pintype "passive"))
      (node (ref "C28") (pin "1") (pinfunction "1_1") (pintype "passive"))
      (node (ref "C29") (pin "1") (pinfunction "1_1") (pintype "passive"))
      (node (ref "C31") (pin "1") (pinfunction "1_1") (pintype "passive"))
      (node (ref "IC10") (pin "4") (pinfunction "V-_4") (pintype "power_in"))
      (node (ref "IC11") (pin "4") (pinfunction "V-_4") (pintype "power_in"))
      (node (ref "IC15") (pin "4") (pinfunction "V-_4") (pintype "power_in"))
      (node (ref "IC7") (pin "5") (pinfunction "OUT_5") (pintype "bidirectional"))
      (node (ref "IC8") (pin "7") (pinfunction "V-_7") (pintype "power_in"))
      (node (ref "IC9") (pin "4") (pinfunction "V-_4") (pintype "power_in"))
      (node (ref "JP1") (pin "3") (pinfunction "3_3") (pintype "passive"))
      (node (ref "R27") (pin "P$2") (pinfunction "2_P$2") (pintype "passive"))
      (node (ref "R31") (pin "P$1") (pinfunction "1_P$1") (pintype "passive"))
      (node (ref "R35") (pin "P$2") (pinfunction "2_P$2") (pintype "passive"))
      (node (ref "R40") (pin "P$2") (pinfunction "2_P$2") (pintype "passive"))
      (node (ref "R46") (pin "P$2") (pinfunction "2_P$2") (pintype "passive"))
      (node (ref "T1") (pin "2") (pinfunction "E_2") (pintype "passive"))
      (node (ref "TP1") (pin "P$1") (pinfunction "P$1_P$1") (pintype "bidirectional"))
    )
    (net (code "6") (name "-18V") (class "Default")
      (node (ref "C18") (pin "2") (pinfunction "2_2") (pintype "passive"))
      (node (ref "IC13") (pin "4") (pinfunction "4_4") (pintype "input"))
      (node (ref "IC6") (pin "5") (pinfunction "OUT_5") (pintype "bidirectional"))
      (node (ref "JP1") (pin "4") (pinfunction "4_4") (pintype "passive"))
      (node (ref "R25") (pin "P$2") (pinfunction "2_P$2") (pintype "passive"))
      (node (ref "TP2") (pin "P$1") (pinfunction "P$1_P$1") (pintype "bidirectional"))
    )
    (net (code "7") (name "0V") (class "Default")
      (node (ref "C12") (pin "2") (pinfunction "2_2") (pintype "passive"))
      (node (ref "C13") (pin "1") (pinfunction "1_1") (pintype "passive"))
      (node (ref "C3") (pin "2") (pinfunction "2_2") (pintype "passive"))
      (node (ref "C9") (pin "2") (pinfunction "2_2") (pintype "passive"))
      (node (ref "IC3") (pin "1") (pinfunction "PGND_1") (pintype "bidirectional"))
      (node (ref "J1") (pin "1") (pinfunction "S_1") (pintype "passive"))
      (node (ref "L1") (pin "P$1") (pinfunction "P$1_P$1") (pintype "bidirectional"))
      (node (ref "R11") (pin "P$2") (pinfunction "2_P$2") (pintype "passive"))
      (node (ref "R2") (pin "P$2") (pinfunction "2_P$2") (pintype "passive"))
      (node (ref "R4") (pin "P$2") (pinfunction "2_P$2") (pintype "passive"))
      (node (ref "R9") (pin "P$2") (pinfunction "2_P$2") (pintype "passive"))
    )
    (net (code "8") (name "AD_C1") (class "Default")
      (node (ref "IC20") (pin "29") (pinfunction "PA8_29") (pintype "bidirectional"))
      (node (ref "R58") (pin "P$2") (pinfunction "2_P$2") (pintype "passive"))
    )
    (net (code "9") (name "AD_C2") (class "Default")
      (node (ref "IC20") (pin "30") (pinfunction "PA9_30") (pintype "bidirectional"))
      (node (ref "R59") (pin "P$2") (pinfunction "2_P$2") (pintype "passive"))
    )
    (net (code "10") (name "AD_C3") (class "Default")
      (node (ref "IC20") (pin "31") (pinfunction "PA10_31") (pintype "bidirectional"))
      (node (ref "R60") (pin "P$2") (pinfunction "2_P$2") (pintype "passive"))
    )
    (net (code "11") (name "AD_COMP") (class "Default")
      (node (ref "IC16") (pin "7") (pinfunction "OUT_7") (pintype "output"))
      (node (ref "R49") (pin "P$1") (pinfunction "1_P$1") (pintype "passive"))
      (node (ref "R53") (pin "P$1") (pinfunction "1_P$1") (pintype "passive"))
      (node (ref "TP7") (pin "P$1") (pinfunction "P$1_P$1") (pintype "bidirectional"))
    )
    (net (code "12") (name "AD_ID") (class "Default")
      (node (ref "IC9") (pin "16") (pinfunction "IN_16") (pintype "input"))
      (node (ref "R56") (pin "P$1") (pinfunction "1_P$1") (pintype "passive"))
    )
    (net (code "13") (name "AD_IIN") (class "Default")
      (node (ref "IC9") (pin "1") (pinfunction "IN_1") (pintype "input"))
      (node (ref "R54") (pin "P$1") (pinfunction "1_P$1") (pintype "passive"))
    )
    (net (code "14") (name "AD_IN") (class "Default")
      (node (ref "JP2") (pin "2") (pinfunction "2_2") (pintype "passive"))
      (node (ref "RN2") (pin "8") (pinfunction "R1B_8") (pintype "bidirectional"))
    )
    (net (code "15") (name "AD_IRN") (class "Default")
      (node (ref "IC9") (pin "8") (pinfunction "IN_8") (pintype "input"))
      (node (ref "R55") (pin "P$1") (pinfunction "1_P$1") (pintype "passive"))
    )
    (net (code "16") (name "AD_IRP") (class "Default")
      (node (ref "IC9") (pin "9") (pinfunction "IN_9") (pintype "input"))
      (node (ref "R57") (pin "P$1") (pinfunction "1_P$1") (pintype "passive"))
    )
    (net (code "17") (name "AD_REF+") (class "Default")
      (node (ref "IC11") (pin "7") (pinfunction "OUT_7") (pintype "output"))
      (node (ref "RN2") (pin "4") (pinfunction "R4A_4") (pintype "bidirectional"))
      (node (ref "RN3") (pin "1") (pinfunction "R1A_1") (pintype "bidirectional"))
      (node (ref "RN3") (pin "2") (pinfunction "R2A_2") (pintype "bidirectional"))
      (node (ref "TP8") (pin "P$1") (pinfunction "P$1_P$1") (pintype "bidirectional"))
    )
    (net (code "18") (name "AD_REF-") (class "Default")
      (node (ref "IC11") (pin "1") (pinfunction "OUT_1") (pintype "output"))
      (node (ref "IC11") (pin "2") (pinfunction "-IN_2") (pintype "input"))
      (node (ref "RN2") (pin "3") (pinfunction "R3A_3") (pintype "bidirectional"))
      (node (ref "RN3") (pin "3") (pinfunction "R3A_3") (pintype "bidirectional"))
      (node (ref "RN3") (pin "4") (pinfunction "R4A_4") (pintype "bidirectional"))
      (node (ref "TP9") (pin "P$1") (pinfunction "P$1_P$1") (pintype "bidirectional"))
    )
    (net (code "19") (name "AD_RFS") (class "Default")
      (node (ref "R30") (pin "P$2") (pinfunction "2_P$2") (pintype "passive"))
      (node (ref "T2") (pin "3") (pinfunction "E_3") (pintype "passive"))
    )
    (net (code "20") (name "AGND") (class "Default")
      (node (ref "C11") (pin "1") (pinfunction "1_1") (pintype "passive"))
      (node (ref "C15") (pin "2") (pinfunction "2_2") (pintype "passive"))
      (node (ref "C16") (pin "2") (pinfunction "2_2") (pintype "passive"))
      (node (ref "C17") (pin "2") (pinfunction "2_2") (pintype "passive"))
      (node (ref "C18") (pin "1") (pinfunction "1_1") (pintype "passive"))
      (node (ref "C19") (pin "1") (pinfunction "1_1") (pintype "passive"))
      (node (ref "C24") (pin "2") (pinfunction "2_2") (pintype "passive"))
      (node (ref "C29") (pin "2") (pinfunction "2_2") (pintype "passive"))
      (node (ref "C6") (pin "1") (pinfunction "1_1") (pintype "passive"))
      (node (ref "IC11") (pin "5") (pinfunction "+IN_5") (pintype "input"))
      (node (ref "IC12") (pin "3") (pinfunction "+IN_3") (pintype "input"))
      (node (ref "IC13") (pin "1") (pinfunction "1_1") (pintype "input"))
      (node (ref "IC14") (pin "3") (pinfunction "+IN_3") (pintype "input"))
      (node (ref "IC15") (pin "7") (pinfunction "V+_7") (pintype "power_in"))
      (node (ref "IC17") (pin "3") (pinfunction "A_3") (pintype "bidirectional"))
      (node (ref "IC3") (pin "15") (pinfunction "AGND_15") (pintype "bidirectional"))
      (node (ref "IC3") (pin "4") (pinfunction "SYNC/FREQ_4") (pintype "bidirectional"))
      (node (ref "IC3") (pin "EP") (pinfunction "AGND_EP") (pintype "bidirectional"))
      (node (ref "IC5") (pin "2") (pinfunction "GND_2") (pintype "bidirectional"))
      (node (ref "IC6") (pin "1") (pinfunction "GND_1") (pintype "bidirectional"))
      (node (ref "IC7") (pin "1") (pinfunction "GND_1") (pintype "bidirectional"))
      (node (ref "IC8") (pin "3") (pinfunction "GND_3") (pintype "power_in"))
      (node (ref "IC9") (pin "5") (pinfunction "GND_5") (pintype "power_in"))
      (node (ref "JP1") (pin "2") (pinfunction "2_2") (pintype "passive"))
      (node (ref "JP2") (pin "3") (pinfunction "3_3") (pintype "passive"))
      (node (ref "R17") (pin "P$1") (pinfunction "1_P$1") (pintype "passive"))
      (node (ref "R18") (pin "P$2") (pinfunction "2_P$2") (pintype "passive"))
      (node (ref "R23") (pin "P$2") (pinfunction "2_P$2") (pintype "passive"))
      (node (ref "R28") (pin "P$2") (pinfunction "2_P$2") (pintype "passive"))
      (node (ref "R29") (pin "P$2") (pinfunction "2_P$2") (pintype "passive"))
      (node (ref "R32") (pin "P$2") (pinfunction "2_P$2") (pintype "passive"))
      (node (ref "R43") (pin "P$1") (pinfunction "1_P$1") (pintype "passive"))
      (node (ref "R45") (pin "P$2") (pinfunction "2_P$2") (pintype "passive"))
      (node (ref "R52") (pin "P$1") (pinfunction "1_P$1") (pintype "passive"))
      (node (ref "R6") (pin "P$2") (pinfunction "2_P$2") (pintype "passive"))
      (node (ref "R7") (pin "P$2") (pinfunction "2_P$2") (pintype "passive"))
      (node (ref "R9") (pin "P$1") (pinfunction "1_P$1") (pintype "passive"))
      (node (ref "RN1") (pin "6") (pinfunction "R3B_6") (pintype "bidirectional"))
      (node (ref "RN1") (pin "EP") (pinfunction "SH_EP") (pintype "bidirectional"))
      (node (ref "RN2") (pin "EP") (pinfunction "SH_EP") (pintype "bidirectional"))
      (node (ref "RN3") (pin "EP") (pinfunction "SH_EP") (pintype "bidirectional"))
      (node (ref "TP4") (pin "P$1") (pinfunction "P$1_P$1") (pintype "bidirectional"))
    )
    (net (code "21") (name "ANA_1") (class "Default")
      (node (ref "C48") (pin "P$1") (pinfunction "1_P$1") (pintype "passive"))
      (node (ref "IC20") (pin "25") (pinfunction "PB12_25") (pintype "bidirectional"))
      (node (ref "R80") (pin "P$2") (pinfunction "2_P$2") (pintype "passive"))
    )
    (net (code "22") (name "DGND") (class "Default")
      (node (ref "C10") (pin "1") (pinfunction "1_1") (pintype "passive"))
      (node (ref "C14") (pin "1") (pinfunction "1_1") (pintype "passive"))
      (node (ref "C32") (pin "1") (pinfunction "1_1") (pintype "passive"))
      (node (ref "C33") (pin "1") (pinfunction "1_1") (pintype "passive"))
      (node (ref "C34") (pin "1") (pinfunction "1_1") (pintype "passive"))
      (node (ref "C35") (pin "1") (pinfunction "1_1") (pintype "passive"))
      (node (ref "C36") (pin "1") (pinfunction "1_1") (pintype "passive"))
      (node (ref "C37") (pin "1") (pinfunction "1_1") (pintype "passive"))
      (node (ref "C38") (pin "1") (pinfunction "1_1") (pintype "passive"))
      (node (ref "C39") (pin "1") (pinfunction "1_1") (pintype "passive"))
      (node (ref "CON1") (pin "10") (pinfunction "10_10") (pintype "bidirectional"))
      (node (ref "CON1") (pin "2") (pinfunction "2_2") (pintype "bidirectional"))
      (node (ref "CON1") (pin "4") (pinfunction "4_4") (pintype "bidirectional"))
      (node (ref "CON1") (pin "6") (pinfunction "6_6") (pintype "bidirectional"))
      (node (ref "CON1") (pin "8") (pinfunction "8_8") (pintype "bidirectional"))
      (node (ref "IC16") (pin "1") (pinfunction "GND_1") (pintype "passive"))
      (node (ref "IC18") (pin "22") (pinfunction "GND_22") (pintype "bidirectional"))
      (node (ref "IC18") (pin "33") (pinfunction "GND_33") (pintype "bidirectional"))
      (node (ref "IC18") (pin "44") (pinfunction "GND_44") (pintype "bidirectional"))
      (node (ref "IC18") (pin "56") (pinfunction "GND_56") (pintype "bidirectional"))
      (node (ref "IC18") (pin "6") (pinfunction "GND_6") (pintype "bidirectional"))
      (node (ref "IC18") (pin "72") (pinfunction "GND_72") (pintype "bidirectional"))
      (node (ref "IC18") (pin "79") (pinfunction "GND_79") (pintype "bidirectional"))
      (node (ref "IC18") (pin "92") (pinfunction "GND_92") (pintype "bidirectional"))
      (node (ref "IC4") (pin "2") (pinfunction "GND_2") (pintype "bidirectional"))
      (node (ref "OSC1") (pin "2") (pinfunction "GND_2") (pintype "bidirectional"))
      (node (ref "R11") (pin "P$1") (pinfunction "1_P$1") (pintype "passive"))
      (node (ref "R65") (pin "P$2") (pinfunction "2_P$2") (pintype "passive"))
    )
    (net (code "23") (name "D_A0") (class "Default")
      (node (ref "IC20") (pin "19") (pinfunction "PB1_19") (pintype "bidirectional"))
      (node (ref "LCD1") (pin "38") (pinfunction "A0_38") (pintype "bidirectional"))
    )
    (net (code "24") (name "D_BK") (class "Default")
      (node (ref "IC20") (pin "22") (pinfunction "PB11_22") (pintype "bidirectional"))
      (node (ref "R78") (pin "P$2") (pinfunction "2_P$2") (pintype "passive"))
    )
    (net (code "25") (name "D_CLK") (class "Default")
      (node (ref "IC20") (pin "18") (pinfunction "PB0_18") (pintype "bidirectional"))
      (node (ref "LCD1") (pin "37") (pinfunction "SCL_37") (pintype "bidirectional"))
    )
    (net (code "26") (name "D_CS") (class "Default")
      (node (ref "IC20") (pin "21") (pinfunction "PB10_21") (pintype "bidirectional"))
      (node (ref "LCD1") (pin "40") (pinfunction "CS1B_40") (pintype "bidirectional"))
    )
    (net (code "27") (name "D_RST") (class "Default")
      (node (ref "IC20") (pin "20") (pinfunction "PB2_20") (pintype "bidirectional"))
      (node (ref "LCD1") (pin "39") (pinfunction "RST_39") (pintype "bidirectional"))
    )
    (net (code "28") (name "D_SI") (class "Default")
      (node (ref "IC20") (pin "17") (pinfunction "PA7_17") (pintype "bidirectional"))
      (node (ref "LCD1") (pin "36") (pinfunction "SI_36") (pintype "bidirectional"))
    )
    (net (code "29") (name "EX_D1") (class "Default")
      (node (ref "IC20") (pin "14") (pinfunction "PA4_14") (pintype "bidirectional"))
      (node (ref "JP3") (pin "3") (pinfunction "3_3") (pintype "passive"))
    )
    (net (code "30") (name "EX_D2") (class "Default")
      (node (ref "IC20") (pin "15") (pinfunction "PA5_15") (pintype "bidirectional"))
      (node (ref "JP3") (pin "4") (pinfunction "4_4") (pintype "passive"))
    )
    (net (code "31") (name "EX_D3") (class "Default")
      (node (ref "IC20") (pin "16") (pinfunction "PA6_16") (pintype "bidirectional"))
      (node (ref "JP3") (pin "5") (pinfunction "5_5") (pintype "passive"))
    )
    (net (code "32") (name "EX_RX") (class "Default")
      (node (ref "IC20") (pin "13") (pinfunction "PA3_13") (pintype "bidirectional"))
      (node (ref "JP3") (pin "2") (pinfunction "2_2") (pintype "passive"))
    )
    (net (code "33") (name "EX_TX") (class "Default")
      (node (ref "IC20") (pin "12") (pinfunction "PA2_12") (pintype "bidirectional"))
      (node (ref "JP3") (pin "1") (pinfunction "1_1") (pintype "passive"))
    )
    (net (code "34") (name "GND") (class "Default")
      (node (ref "C1") (pin "1") (pinfunction "1_1") (pintype "passive"))
      (node (ref "C2") (pin "1") (pinfunction "1_1") (pintype "passive"))
      (node (ref "C40") (pin "2") (pinfunction "2_2") (pintype "passive"))
      (node (ref "C41") (pin "2") (pinfunction "2_2") (pintype "passive"))
      (node (ref "C42") (pin "2") (pinfunction "2_2") (pintype "passive"))
      (node (ref "C43") (pin "2") (pinfunction "2_2") (pintype "passive"))
      (node (ref "C44") (pin "2") (pinfunction "2_2") (pintype "passive"))
      (node (ref "C45") (pin "P$2") (pinfunction "2_P$2") (pintype "passive"))
      (node (ref "C46") (pin "2") (pinfunction "2_2") (pintype "passive"))
      (node (ref "C47") (pin "2") (pinfunction "2_2") (pintype "passive"))
      (node (ref "C48") (pin "P$2") (pinfunction "2_P$2") (pintype "passive"))
      (node (ref "C49") (pin "2") (pinfunction "2_2") (pintype "passive"))
      (node (ref "C50") (pin "2") (pinfunction "2_2") (pintype "passive"))
      (node (ref "C51") (pin "2") (pinfunction "2_2") (pintype "passive"))
      (node (ref "C52") (pin "2") (pinfunction "2_2") (pintype "passive"))
      (node (ref "C55") (pin "2") (pinfunction "2_2") (pintype "passive"))
      (node (ref "C56") (pin "2") (pinfunction "2_2") (pintype "passive"))
      (node (ref "C7") (pin "1") (pinfunction "1_1") (pintype "passive"))
      (node (ref "C8") (pin "1") (pinfunction "1_1") (pintype "passive"))
      (node (ref "IC1") (pin "1") (pinfunction "VSS_1") (pintype "input"))
      (node (ref "IC19") (pin "4") (pinfunction "VSS_4") (pintype "power_in"))
      (node (ref "IC2") (pin "1") (pinfunction "VSS_1") (pintype "input"))
      (node (ref "IC20") (pin "23") (pinfunction "VSS_1_23") (pintype "bidirectional"))
      (node (ref "IC20") (pin "35") (pinfunction "VSS_2_35") (pintype "bidirectional"))
      (node (ref "IC20") (pin "47") (pinfunction "VSS_3_47") (pintype "bidirectional"))
      (node (ref "IC20") (pin "8") (pinfunction "VSSA_8") (pintype "bidirectional"))
      (node (ref "IC21") (pin "2") (pinfunction "VSS_2") (pintype "power_in"))
      (node (ref "JP3") (pin "8") (pinfunction "8_8") (pintype "passive"))
      (node (ref "JP4") (pin "4") (pinfunction "4_4") (pintype "passive"))
      (node (ref "K1") (pin "P$1") (pinfunction "P$1_P$1") (pintype "bidirectional"))
      (node (ref "K2") (pin "P$1") (pinfunction "P$1_P$1") (pintype "bidirectional"))
      (node (ref "K3") (pin "P$1") (pinfunction "P$1_P$1") (pintype "bidirectional"))
      (node (ref "K4") (pin "P$1") (pinfunction "P$1_P$1") (pintype "bidirectional"))
      (node (ref "K5") (pin "P$1") (pinfunction "P$1_P$1") (pintype "bidirectional"))
      (node (ref "K6") (pin "P$1") (pinfunction "P$1_P$1") (pintype "bidirectional"))
      (node (ref "LCD1") (pin "26") (pinfunction "VSS_26") (pintype "power_in"))
      (node (ref "LCD1") (pin "33") (pinfunction "VSS1_33") (pintype "power_in"))
      (node (ref "R2") (pin "P$1") (pinfunction "1_P$1") (pintype "passive"))
      (node (ref "R4") (pin "P$1") (pinfunction "1_P$1") (pintype "passive"))
      (node (ref "R67") (pin "P$2") (pinfunction "2_P$2") (pintype "passive"))
      (node (ref "R74") (pin "P$2") (pinfunction "2_P$2") (pintype "passive"))
      (node (ref "T3") (pin "2") (pinfunction "E_2") (pintype "passive"))
      (node (ref "TP20") (pin "P$1") (pinfunction "P$1_P$1") (pintype "bidirectional"))
    )
    (net (code "35") (name "K1") (class "Default")
      (node (ref "IC20") (pin "27") (pinfunction "PB14_27") (pintype "bidirectional"))
      (node (ref "K1") (pin "P$2") (pinfunction "P$2_P$2") (pintype "bidirectional"))
      (node (ref "R68") (pin "P$1") (pinfunction "1_P$1") (pintype "passive"))
    )
    (net (code "36") (name "K2") (class "Default")
      (node (ref "IC20") (pin "26") (pinfunction "PB13_26") (pintype "bidirectional"))
      (node (ref "K2") (pin "P$2") (pinfunction "P$2_P$2") (pintype "bidirectional"))
      (node (ref "R70") (pin "P$1") (pinfunction "1_P$1") (pintype "passive"))
    )
    (net (code "37") (name "K3") (class "Default")
      (node (ref "IC20") (pin "11") (pinfunction "PA1_11") (pintype "bidirectional"))
      (node (ref "K3") (pin "P$2") (pinfunction "P$2_P$2") (pintype "bidirectional"))
      (node (ref "R71") (pin "P$1") (pinfunction "1_P$1") (pintype "passive"))
    )
    (net (code "38") (name "K4") (class "Default")
      (node (ref "IC20") (pin "10") (pinfunction "PA0-WKUP1_10") (pintype "bidirectional"))
      (node (ref "K4") (pin "P$2") (pinfunction "P$2_P$2") (pintype "bidirectional"))
      (node (ref "R72") (pin "P$1") (pinfunction "1_P$1") (pintype "passive"))
    )
    (net (code "39") (name "K5") (class "Default")
      (node (ref "IC20") (pin "28") (pinfunction "PB15_28") (pintype "bidirectional"))
      (node (ref "K5") (pin "P$2") (pinfunction "P$2_P$2") (pintype "bidirectional"))
      (node (ref "R75") (pin "P$1") (pinfunction "1_P$1") (pintype "passive"))
    )
    (net (code "40") (name "K6") (class "Default")
      (node (ref "IC20") (pin "38") (pinfunction "PA15_38") (pintype "bidirectional"))
      (node (ref "K6") (pin "P$2") (pinfunction "P$2_P$2") (pintype "bidirectional"))
      (node (ref "R76") (pin "P$1") (pinfunction "1_P$1") (pintype "passive"))
    )
    (net (code "41") (name "Net-(C25-1)") (class "Default")
      (node (ref "C25") (pin "P$1") (pinfunction "1_P$1") (pintype "passive"))
      (node (ref "D4") (pin "A") (pinfunction "A_A") (pintype "input"))
      (node (ref "D5") (pin "K") (pinfunction "K_K") (pintype "output"))
      (node (ref "IC14") (pin "2") (pinfunction "-IN_2") (pintype "input"))
      (node (ref "R36") (pin "P$2") (pinfunction "2_P$2") (pintype "passive"))
      (node (ref "R38") (pin "P$1") (pinfunction "1_P$1") (pintype "passive"))
    )
    (net (code "42") (name "Net-(C25-2)") (class "Default")
      (node (ref "C25") (pin "P$2") (pinfunction "2_P$2") (pintype "passive"))
      (node (ref "D4") (pin "K") (pinfunction "K_K") (pintype "output"))
      (node (ref "D5") (pin "A") (pinfunction "A_A") (pintype "input"))
      (node (ref "IC14") (pin "6") (pinfunction "OUT_6") (pintype "output"))
      (node (ref "R38") (pin "P$2") (pinfunction "2_P$2") (pintype "passive"))
      (node (ref "R44") (pin "P$1") (pinfunction "1_P$1") (pintype "passive"))
      (node (ref "TP6") (pin "P$1") (pinfunction "P$1_P$1") (pintype "bidirectional"))
    )
    (net (code "43") (name "Net-(C27-1)") (class "Default")
      (node (ref "C27") (pin "P$1") (pinfunction "1_P$1") (pintype "passive"))
      (node (ref "IC14") (pin "8") (pinfunction "OPT_8") (pintype "passive"))
    )
    (net (code "44") (name "Net-(C27-2)") (class "Default")
      (node (ref "C27") (pin "P$2") (pinfunction "2_P$2") (pintype "passive"))
      (node (ref "IC14") (pin "1") (pinfunction "ON1_1") (pintype "passive"))
    )
    (net (code "45") (name "Net-(C45-1)") (class "Default")
      (node (ref "C45") (pin "P$1") (pinfunction "1_P$1") (pintype "passive"))
      (node (ref "IC21") (pin "3") (pinfunction "NEIN+_3") (pintype "input"))
      (node (ref "R73") (pin "P$2") (pinfunction "2_P$2") (pintype "passive"))
      (node (ref "R74") (pin "P$1") (pinfunction "1_P$1") (pintype "passive"))
    )
    (net (code "46") (name "Net-(IC3-COMP1)") (class "Default")
      (node (ref "C4") (pin "2") (pinfunction "2_2") (pintype "passive"))
      (node (ref "IC3") (pin "8") (pinfunction "COMP1_8") (pintype "bidirectional"))
    )
    (net (code "47") (name "Net-(IC3-COMP2)") (class "Default")
      (node (ref "C5") (pin "2") (pinfunction "2_2") (pintype "passive"))
      (node (ref "IC3") (pin "12") (pinfunction "COMP2_12") (pintype "bidirectional"))
    )
    (net (code "48") (name "Net-(IC3-EN1)") (class "Default")
      (node (ref "IC3") (pin "11") (pinfunction "EN2_11") (pintype "bidirectional"))
      (node (ref "IC3") (pin "9") (pinfunction "EN1_9") (pintype "bidirectional"))
      (node (ref "R8") (pin "P$1") (pinfunction "1_P$1") (pintype "passive"))
    )
    (net (code "49") (name "Net-(IC3-FB1)") (class "Default")
      (node (ref "IC3") (pin "7") (pinfunction "FB1_7") (pintype "bidirectional"))
      (node (ref "R13") (pin "P$2") (pinfunction "2_P$2") (pintype "passive"))
      (node (ref "R14") (pin "P$1") (pinfunction "1_P$1") (pintype "passive"))
    )
    (net (code "50") (name "Net-(IC3-FB2)") (class "Default")
      (node (ref "IC3") (pin "13") (pinfunction "FB2_13") (pintype "bidirectional"))
      (node (ref "R15") (pin "P$1") (pinfunction "1_P$1") (pintype "passive"))
      (node (ref "R16") (pin "P$2") (pinfunction "2_P$2") (pintype "passive"))
    )
    (net (code "51") (name "Net-(IC3-INBK)") (class "Default")
      (node (ref "IC3") (pin "3") (pinfunction "INBK_3") (pintype "bidirectional"))
      (node (ref "L2") (pin "P$1") (pinfunction "P$1_P$1") (pintype "bidirectional"))
    )
    (net (code "52") (name "Net-(IC3-PVIN1)") (class "Default")
      (node (ref "C3") (pin "1") (pinfunction "1_1") (pintype "passive"))
      (node (ref "C9") (pin "1") (pinfunction "1_1") (pintype "passive"))
      (node (ref "IC3") (pin "17") (pinfunction "PVIN1_17") (pintype "bidirectional"))
      (node (ref "IC3") (pin "18") (pinfunction "PVINSYS_18") (pintype "bidirectional"))
      (node (ref "IC3") (pin "19") (pinfunction "PVIN2_19") (pintype "bidirectional"))
      (node (ref "R5") (pin "P$1") (pinfunction "1_P$1") (pintype "passive"))
    )
    (net (code "53") (name "Net-(IC3-SW1)") (class "Default")
      (node (ref "D2") (pin "A") (pinfunction "A_A") (pintype "passive"))
      (node (ref "IC3") (pin "2") (pinfunction "SW1_2") (pintype "bidirectional"))
      (node (ref "L2") (pin "P$2") (pinfunction "P$2_P$2") (pintype "bidirectional"))
    )
    (net (code "54") (name "Net-(IC3-SW2)") (class "Default")
      (node (ref "D1") (pin "C") (pinfunction "C_C") (pintype "passive"))
      (node (ref "IC3") (pin "20") (pinfunction "SW2_20") (pintype "bidirectional"))
      (node (ref "L1") (pin "P$2") (pinfunction "P$2_P$2") (pintype "bidirectional"))
    )
    (net (code "55") (name "Net-(IC3-VREF)") (class "Default")
      (node (ref "C11") (pin "2") (pinfunction "2_2") (pintype "passive"))
      (node (ref "IC3") (pin "14") (pinfunction "VREF_14") (pintype "bidirectional"))
    )
    (net (code "56") (name "Net-(IC3-VREG)") (class "Default")
      (node (ref "C6") (pin "2") (pinfunction "2_2") (pintype "passive"))
      (node (ref "IC3") (pin "16") (pinfunction "VREG_16") (pintype "bidirectional"))
    )
    (net (code "57") (name "Net-(IC4-IN)") (class "Default")
      (node (ref "C10") (pin "2") (pinfunction "2_2") (pintype "passive"))
      (node (ref "IC4") (pin "1") (pinfunction "IN_1") (pintype "bidirectional"))
      (node (ref "R10") (pin "P$1") (pinfunction "1_P$1") (pintype "passive"))
    )
    (net (code "58") (name "Net-(IC4-~{SHDN})") (class "Default")
      (node (ref "IC4") (pin "3") (pinfunction "~{SHDN}_3") (pintype "bidirectional"))
      (node (ref "R12") (pin "P$2") (pinfunction "2_P$2") (pintype "passive"))
    )
    (net (code "59") (name "Net-(IC5-ADJ)") (class "Default")
      (node (ref "IC5") (pin "4") (pinfunction "ADJ_4") (pintype "bidirectional"))
      (node (ref "R21") (pin "P$1") (pinfunction "1_P$1") (pintype "passive"))
      (node (ref "R22") (pin "P$1") (pinfunction "1_P$1") (pintype "passive"))
    )
    (net (code "60") (name "Net-(IC5-EN)") (class "Default")
      (node (ref "C15") (pin "1") (pinfunction "1_1") (pintype "passive"))
      (node (ref "IC5") (pin "1") (pinfunction "VIN_1") (pintype "bidirectional"))
      (node (ref "IC5") (pin "3") (pinfunction "EN_3") (pintype "bidirectional"))
      (node (ref "R19") (pin "P$1") (pinfunction "1_P$1") (pintype "passive"))
    )
    (net (code "61") (name "Net-(IC6-ADJ)") (class "Default")
      (node (ref "IC6") (pin "4") (pinfunction "ADJ_4") (pintype "bidirectional"))
      (node (ref "R24") (pin "P$1") (pinfunction "1_P$1") (pintype "passive"))
      (node (ref "R25") (pin "P$1") (pinfunction "1_P$1") (pintype "passive"))
    )
    (net (code "62") (name "Net-(IC6-EN)") (class "Default")
      (node (ref "C16") (pin "1") (pinfunction "1_1") (pintype "passive"))
      (node (ref "IC6") (pin "2") (pinfunction "VIN_2") (pintype "bidirectional"))
      (node (ref "IC6") (pin "3") (pinfunction "EN_3") (pintype "bidirectional"))
      (node (ref "IC7") (pin "2") (pinfunction "VIN_2") (pintype "bidirectional"))
      (node (ref "IC7") (pin "3") (pinfunction "EN_3") (pintype "bidirectional"))
      (node (ref "R20") (pin "P$1") (pinfunction "1_P$1") (pintype "passive"))
    )
    (net (code "63") (name "Net-(IC7-ADJ)") (class "Default")
      (node (ref "IC7") (pin "4") (pinfunction "ADJ_4") (pintype "bidirectional"))
      (node (ref "R26") (pin "P$1") (pinfunction "1_P$1") (pintype "passive"))
      (node (ref "R27") (pin "P$1") (pinfunction "1_P$1") (pintype "passive"))
    )
    (net (code "64") (name "Net-(IC8A-S1)") (class "Default")
      (node (ref "IC8") (pin "2") (pinfunction "S1_2") (pintype "bidirectional"))
      (node (ref "RN1") (pin "7") (pinfunction "R2B_7") (pintype "bidirectional"))
      (node (ref "RN1") (pin "8") (pinfunction "R1B_8") (pintype "bidirectional"))
    )
    (net (code "65") (name "Net-(IC9A-D)") (class "Default")
      (node (ref "IC9") (pin "2") (pinfunction "D_2") (pintype "bidirectional"))
      (node (ref "RN2") (pin "7") (pinfunction "R2B_7") (pintype "bidirectional"))
    )
    (net (code "66") (name "Net-(IC9C-S)") (class "Default")
      (node (ref "IC9") (pin "11") (pinfunction "S_11") (pintype "bidirectional"))
      (node (ref "RN2") (pin "6") (pinfunction "R3B_6") (pintype "bidirectional"))
    )
    (net (code "67") (name "Net-(IC9D-S)") (class "Default")
      (node (ref "IC9") (pin "6") (pinfunction "S_6") (pintype "bidirectional"))
      (node (ref "RN2") (pin "5") (pinfunction "R4B_5") (pintype "bidirectional"))
    )
    (net (code "68") (name "Net-(IC11A-+IN)") (class "Default")
      (node (ref "IC11") (pin "3") (pinfunction "+IN_3") (pintype "input"))
      (node (ref "IC8") (pin "1") (pinfunction "D_1") (pintype "bidirectional"))
    )
    (net (code "69") (name "Net-(IC11B--IN)") (class "Default")
      (node (ref "IC11") (pin "6") (pinfunction "-IN_6") (pintype "input"))
      (node (ref "RN3") (pin "5") (pinfunction "R4B_5") (pintype "bidirectional"))
      (node (ref "RN3") (pin "6") (pinfunction "R3B_6") (pintype "bidirectional"))
      (node (ref "RN3") (pin "7") (pinfunction "R2B_7") (pintype "bidirectional"))
      (node (ref "RN3") (pin "8") (pinfunction "R1B_8") (pintype "bidirectional"))
    )
    (net (code "70") (name "Net-(IC12--IN)") (class "Default")
      (node (ref "C22") (pin "1") (pinfunction "1_1") (pintype "passive"))
      (node (ref "IC12") (pin "2") (pinfunction "-IN_2") (pintype "input"))
      (node (ref "IC9") (pin "10") (pinfunction "D_10") (pintype "bidirectional"))
      (node (ref "IC9") (pin "14") (pinfunction "S_14") (pintype "bidirectional"))
      (node (ref "IC9") (pin "3") (pinfunction "S_3") (pintype "bidirectional"))
      (node (ref "IC9") (pin "7") (pinfunction "D_7") (pintype "bidirectional"))
    )
    (net (code "71") (name "Net-(IC12-OUT)") (class "Default")
      (node (ref "C22") (pin "2") (pinfunction "2_2") (pintype "passive"))
      (node (ref "IC12") (pin "6") (pinfunction "OUT_6") (pintype "output"))
      (node (ref "IC9") (pin "15") (pinfunction "D_15") (pintype "bidirectional"))
      (node (ref "R36") (pin "P$1") (pinfunction "1_P$1") (pintype "passive"))
      (node (ref "TP5") (pin "P$1") (pinfunction "P$1_P$1") (pintype "bidirectional"))
    )
    (net (code "72") (name "Net-(IC12-V+)") (class "Default")
      (node (ref "C23") (pin "2") (pinfunction "2_2") (pintype "passive"))
      (node (ref "IC12") (pin "7") (pinfunction "V+_7") (pintype "power_in"))
      (node (ref "R33") (pin "P$1") (pinfunction "1_P$1") (pintype "passive"))
    )
    (net (code "73") (name "Net-(IC12-V-)") (class "Default")
      (node (ref "C23") (pin "1") (pinfunction "1_1") (pintype "passive"))
      (node (ref "IC12") (pin "4") (pinfunction "V-_4") (pintype "power_in"))
      (node (ref "R35") (pin "P$1") (pinfunction "1_P$1") (pintype "passive"))
    )
    (net (code "74") (name "Net-(IC14-V+)") (class "Default")
      (node (ref "C26") (pin "2") (pinfunction "2_2") (pintype "passive"))
      (node (ref "IC14") (pin "7") (pinfunction "V+_7") (pintype "power_in"))
      (node (ref "R39") (pin "P$1") (pinfunction "1_P$1") (pintype "passive"))
    )
    (net (code "75") (name "Net-(IC14-V-)") (class "Default")
      (node (ref "C26") (pin "1") (pinfunction "1_1") (pintype "passive"))
      (node (ref "IC14") (pin "4") (pinfunction "V-_4") (pintype "power_in"))
      (node (ref "R40") (pin "P$1") (pinfunction "1_P$1") (pintype "passive"))
    )
    (net (code "76") (name "Net-(IC15-+IN)") (class "Default")
      (node (ref "IC13") (pin "2") (pinfunction "2_2") (pintype "input"))
      (node (ref "IC15") (pin "3") (pinfunction "+IN_3") (pintype "input"))
      (node (ref "R37") (pin "P$1") (pinfunction "1_P$1") (pintype "passive"))
      (node (ref "R41") (pin "P$2") (pinfunction "2_P$2") (pintype "passive"))
    )
    (net (code "77") (name "Net-(IC15--IN)") (class "Default")
      (node (ref "IC15") (pin "2") (pinfunction "-IN_2") (pintype "input"))
      (node (ref "R42") (pin "P$2") (pinfunction "2_P$2") (pintype "passive"))
      (node (ref "R43") (pin "P$2") (pinfunction "2_P$2") (pintype "passive"))
    )
    (net (code "78") (name "Net-(IC16-+IN)") (class "Default")
      (node (ref "IC16") (pin "2") (pinfunction "+IN_2") (pintype "input"))
      (node (ref "R44") (pin "P$2") (pinfunction "2_P$2") (pintype "passive"))
    )
    (net (code "79") (name "Net-(IC16--IN)") (class "Default")
      (node (ref "IC16") (pin "3") (pinfunction "-IN_3") (pintype "input"))
      (node (ref "R45") (pin "P$1") (pinfunction "1_P$1") (pintype "passive"))
    )
    (net (code "80") (name "Net-(IC16-ON)") (class "Default")
      (node (ref "IC16") (pin "5") (pinfunction "ON_5") (pintype "passive"))
      (node (ref "R48") (pin "P$1") (pinfunction "1_P$1") (pintype "passive"))
    )
    (net (code "81") (name "Net-(IC16-V-)") (class "Default")
      (node (ref "C30") (pin "2") (pinfunction "2_2") (pintype "passive"))
      (node (ref "IC16") (pin "4") (pinfunction "V-_4") (pintype "power_in"))
      (node (ref "R46") (pin "P$1") (pinfunction "1_P$1") (pintype "passive"))
    )
    (net (code "82") (name "Net-(IC17-C)") (class "Default")
      (node (ref "IC17") (pin "1") (pinfunction "C_1") (pintype "bidirectional"))
      (node (ref "IC8") (pin "5") (pinfunction "VL_5") (pintype "input"))
      (node (ref "IC9") (pin "12") (pinfunction "VL_12") (pintype "input"))
      (node (ref "R50") (pin "P$2") (pinfunction "2_P$2") (pintype "passive"))
      (node (ref "R51") (pin "P$1") (pinfunction "1_P$1") (pintype "passive"))
    )
    (net (code "83") (name "Net-(IC17-R)") (class "Default")
      (node (ref "IC17") (pin "2") (pinfunction "R_2") (pintype "bidirectional"))
      (node (ref "R51") (pin "P$2") (pinfunction "2_P$2") (pintype "passive"))
      (node (ref "R52") (pin "P$2") (pinfunction "2_P$2") (pintype "passive"))
    )
    (net (code "84") (name "Net-(IC18-PB9B)") (class "Default")
      (node (ref "IC18") (pin "35") (pinfunction "PB9B_35") (pintype "bidirectional"))
      (node (ref "R54") (pin "P$2") (pinfunction "2_P$2") (pintype "passive"))
      (node (ref "TP10") (pin "P$1") (pinfunction "P$1_P$1") (pintype "bidirectional"))
    )
    (net (code "85") (name "Net-(IC18-PB11A)") (class "Default")
      (node (ref "IC18") (pin "38") (pinfunction "PB11A_38") (pintype "bidirectional"))
      (node (ref "R55") (pin "P$2") (pinfunction "2_P$2") (pintype "passive"))
      (node (ref "TP12") (pin "P$1") (pinfunction "P$1_P$1") (pintype "bidirectional"))
    )
    (net (code "86") (name "Net-(IC18-PB11C)") (class "Default")
      (node (ref "IC18") (pin "36") (pinfunction "PB11C_36") (pintype "bidirectional"))
      (node (ref "R56") (pin "P$2") (pinfunction "2_P$2") (pintype "passive"))
      (node (ref "TP13") (pin "P$1") (pinfunction "P$1_P$1") (pintype "bidirectional"))
    )
    (net (code "87") (name "Net-(IC18-PB11D)") (class "Default")
      (node (ref "IC18") (pin "37") (pinfunction "PB11D_37") (pintype "bidirectional"))
      (node (ref "R57") (pin "P$2") (pinfunction "2_P$2") (pintype "passive"))
      (node (ref "TP11") (pin "P$1") (pinfunction "P$1_P$1") (pintype "bidirectional"))
    )
    (net (code "88") (name "Net-(IC18-PL3A)") (class "Default")
      (node (ref "IC18") (pin "3") (pinfunction "PL3A_3") (pintype "bidirectional"))
      (node (ref "OSC1") (pin "3") (pinfunction "OUT_3") (pintype "bidirectional"))
    )
    (net (code "89") (name "Net-(IC18-PL5A)") (class "Default")
      (node (ref "IC18") (pin "12") (pinfunction "PL5A_12") (pintype "bidirectional"))
      (node (ref "TP14") (pin "P$1") (pinfunction "P$1_P$1") (pintype "bidirectional"))
    )
    (net (code "90") (name "Net-(IC18-PL5B)") (class "Default")
      (node (ref "IC18") (pin "13") (pinfunction "PL5B_13") (pintype "bidirectional"))
      (node (ref "TP15") (pin "P$1") (pinfunction "P$1_P$1") (pintype "bidirectional"))
    )
    (net (code "91") (name "Net-(IC18-PL5C)") (class "Default")
      (node (ref "IC18") (pin "14") (pinfunction "PL5C_14") (pintype "bidirectional"))
      (node (ref "TP16") (pin "P$1") (pinfunction "P$1_P$1") (pintype "bidirectional"))
    )
    (net (code "92") (name "Net-(IC18-PL5D)") (class "Default")
      (node (ref "IC18") (pin "15") (pinfunction "PL5D_15") (pintype "bidirectional"))
      (node (ref "TP17") (pin "P$1") (pinfunction "P$1_P$1") (pintype "bidirectional"))
    )
    (net (code "93") (name "Net-(IC18-PL8C)") (class "Default")
      (node (ref "IC18") (pin "18") (pinfunction "PL8C_18") (pintype "bidirectional"))
      (node (ref "R53") (pin "P$2") (pinfunction "2_P$2") (pintype "passive"))
    )
    (net (code "94") (name "Net-(IC18-PR5C)") (class "Default")
      (node (ref "IC18") (pin "63") (pinfunction "PR5C_63") (pintype "bidirectional"))
      (node (ref "R62") (pin "P$2") (pinfunction "2_P$2") (pintype "passive"))
    )
    (net (code "95") (name "Net-(IC18-PT10C{slash}TDO)") (class "Default")
      (node (ref "CON1") (pin "3") (pinfunction "3_3") (pintype "bidirectional"))
      (node (ref "IC18") (pin "95") (pinfunction "PT10C/TDO_95") (pintype "bidirectional"))
      (node (ref "R64") (pin "P$2") (pinfunction "2_P$2") (pintype "passive"))
    )
    (net (code "96") (name "Net-(IC18-PT10D{slash}TDI)") (class "Default")
      (node (ref "CON1") (pin "5") (pinfunction "5_5") (pintype "bidirectional"))
      (node (ref "IC18") (pin "94") (pinfunction "PT10D/TDI_94") (pintype "bidirectional"))
      (node (ref "R63") (pin "P$2") (pinfunction "2_P$2") (pintype "passive"))
    )
    (net (code "97") (name "Net-(IC18-PT11C{slash}TCK)") (class "Default")
      (node (ref "CON1") (pin "7") (pinfunction "7_7") (pintype "bidirectional"))
      (node (ref "IC18") (pin "91") (pinfunction "PT11C/TCK_91") (pintype "bidirectional"))
      (node (ref "R65") (pin "P$1") (pinfunction "1_P$1") (pintype "passive"))
    )
    (net (code "98") (name "Net-(IC18-PT11D{slash}TMS)") (class "Default")
      (node (ref "CON1") (pin "9") (pinfunction "9_9") (pintype "bidirectional"))
      (node (ref "IC18") (pin "90") (pinfunction "PT11D/TMS_90") (pintype "bidirectional"))
      (node (ref "R61") (pin "P$2") (pinfunction "2_P$2") (pintype "passive"))
    )
    (net (code "99") (name "Net-(IC18-PT12D)") (class "Default")
      (node (ref "IC18") (pin "85") (pinfunction "PT12D_85") (pintype "bidirectional"))
      (node (ref "R58") (pin "P$1") (pinfunction "1_P$1") (pintype "passive"))
    )
    (net (code "100") (name "Net-(IC18-PT15A)") (class "Default")
      (node (ref "IC18") (pin "84") (pinfunction "PT15A_84") (pintype "bidirectional"))
      (node (ref "R59") (pin "P$1") (pinfunction "1_P$1") (pintype "passive"))
    )
    (net (code "101") (name "Net-(IC18-PT15B)") (class "Default")
      (node (ref "IC18") (pin "83") (pinfunction "PT15B_83") (pintype "bidirectional"))
      (node (ref "R60") (pin "P$1") (pinfunction "1_P$1") (pintype "passive"))
    )
    (net (code "102") (name "Net-(IC19-SCK)") (class "Default")
      (node (ref "IC19") (pin "6") (pinfunction "SCK_6") (pintype "input"))
      (node (ref "IC20") (pin "39") (pinfunction "PB3_39") (pintype "bidirectional"))
    )
    (net (code "103") (name "Net-(IC19-SI)") (class "Default")
      (node (ref "IC19") (pin "5") (pinfunction "SI_5") (pintype "input"))
      (node (ref "IC20") (pin "41") (pinfunction "PB5_41") (pintype "bidirectional"))
    )
    (net (code "104") (name "Net-(IC19-SO)") (class "Default")
      (node (ref "IC19") (pin "2") (pinfunction "SO_2") (pintype "input"))
      (node (ref "IC20") (pin "40") (pinfunction "PB4_40") (pintype "bidirectional"))
    )
    (net (code "105") (name "Net-(IC19-~{CS})") (class "Default")
      (node (ref "IC19") (pin "1") (pinfunction "~{CS}_1") (pintype "input"))
      (node (ref "IC20") (pin "42") (pinfunction "PB6_42") (pintype "bidirectional"))
      (node (ref "R66") (pin "P$2") (pinfunction "2_P$2") (pintype "passive"))
    )
    (net (code "106") (name "Net-(IC20-BOOT0)") (class "Default")
      (node (ref "IC20") (pin "44") (pinfunction "BOOT0_44") (pintype "bidirectional"))
      (node (ref "R67") (pin "P$1") (pinfunction "1_P$1") (pintype "passive"))
    )
    (net (code "107") (name "Net-(IC20-NRST)") (class "Default")
      (node (ref "IC20") (pin "7") (pinfunction "NRST_7") (pintype "bidirectional"))
      (node (ref "R69") (pin "P$1") (pinfunction "1_P$1") (pintype "passive"))
    )
    (net (code "108") (name "Net-(IC20-PA13{slash}SWDIO)") (class "Default")
      (node (ref "IC20") (pin "34") (pinfunction "PA13/SWDIO_34") (pintype "bidirectional"))
      (node (ref "JP4") (pin "1") (pinfunction "1_1") (pintype "passive"))
    )
    (net (code "109") (name "Net-(IC20-PA14{slash}SWCLK)") (class "Default")
      (node (ref "IC20") (pin "37") (pinfunction "PA14/SWCLK_37") (pintype "bidirectional"))
      (node (ref "JP4") (pin "2") (pinfunction "2_2") (pintype "passive"))
    )
    (net (code "110") (name "Net-(IC20-PB8)") (class "Default")
      (node (ref "IC20") (pin "45") (pinfunction "PB8_45") (pintype "bidirectional"))
      (node (ref "TP18") (pin "P$1") (pinfunction "P$1_P$1") (pintype "bidirectional"))
    )
    (net (code "111") (name "Net-(IC20-PB9)") (class "Default")
      (node (ref "IC20") (pin "46") (pinfunction "PB9_46") (pintype "bidirectional"))
      (node (ref "TP19") (pin "P$1") (pinfunction "P$1_P$1") (pintype "bidirectional"))
    )
    (net (code "112") (name "Net-(IC20-PH0-OSC_IN)") (class "Default")
      (node (ref "C42") (pin "1") (pinfunction "1_1") (pintype "passive"))
      (node (ref "IC20") (pin "5") (pinfunction "PH0-OSC_IN_5") (pintype "bidirectional"))
      (node (ref "Q1") (pin "2") (pinfunction "2_2") (pintype "passive"))
    )
    (net (code "113") (name "Net-(IC20-PH1-OSC_OUT)") (class "Default")
      (node (ref "C41") (pin "1") (pinfunction "1_1") (pintype "passive"))
      (node (ref "IC20") (pin "6") (pinfunction "PH1-OSC_OUT_6") (pintype "bidirectional"))
      (node (ref "Q1") (pin "1") (pinfunction "1_1") (pintype "passive"))
    )
    (net (code "114") (name "Net-(IC21A-IN-)") (class "Default")
      (node (ref "IC21") (pin "1") (pinfunction "VYSTUP_1") (pintype "output"))
      (node (ref "IC21") (pin "4") (pinfunction "IN-_4") (pintype "input"))
      (node (ref "R80") (pin "P$1") (pinfunction "1_P$1") (pintype "passive"))
    )
    (net (code "115") (name "Net-(LCD1-A1+)") (class "Default")
      (node (ref "LCD1") (pin "1") (pinfunction "A1+_1") (pintype "bidirectional"))
      (node (ref "R79") (pin "P$1") (pinfunction "1_P$1") (pintype "passive"))
    )
    (net (code "116") (name "Net-(LCD1-A2+)") (class "Default")
      (node (ref "LCD1") (pin "20") (pinfunction "A2+_20") (pintype "bidirectional"))
      (node (ref "R77") (pin "P$1") (pinfunction "1_P$1") (pintype "passive"))
    )
    (net (code "117") (name "Net-(LCD1-C1-)") (class "Default")
      (node (ref "LCD1") (pin "19") (pinfunction "C2-_19") (pintype "bidirectional"))
      (node (ref "LCD1") (pin "2") (pinfunction "C1-_2") (pintype "bidirectional"))
      (node (ref "T3") (pin "3") (pinfunction "C_3") (pintype "passive"))
    )
    (net (code "118") (name "Net-(LCD1-CAP1N)") (class "Default")
      (node (ref "C53") (pin "2") (pinfunction "2_2") (pintype "passive"))
      (node (ref "LCD1") (pin "30") (pinfunction "CAP1N_30") (pintype "bidirectional"))
    )
    (net (code "119") (name "Net-(LCD1-CAP1P)") (class "Default")
      (node (ref "C53") (pin "1") (pinfunction "1_1") (pintype "passive"))
      (node (ref "LCD1") (pin "29") (pinfunction "CAP1P_29") (pintype "bidirectional"))
    )
    (net (code "120") (name "Net-(LCD1-CAP2N)") (class "Default")
      (node (ref "C54") (pin "1") (pinfunction "1_1") (pintype "passive"))
      (node (ref "LCD1") (pin "27") (pinfunction "CAP2N_27") (pintype "bidirectional"))
    )
    (net (code "121") (name "Net-(LCD1-CAP2P)") (class "Default")
      (node (ref "C54") (pin "2") (pinfunction "2_2") (pintype "passive"))
      (node (ref "LCD1") (pin "28") (pinfunction "CAP2P_28") (pintype "bidirectional"))
    )
    (net (code "122") (name "Net-(LCD1-CAP3P)") (class "Default")
      (node (ref "C49") (pin "1") (pinfunction "1_1") (pintype "passive"))
      (node (ref "LCD1") (pin "31") (pinfunction "CAP3P_31") (pintype "bidirectional"))
      (node (ref "LCD1") (pin "32") (pinfunction "VOUT_32") (pintype "bidirectional"))
    )
    (net (code "123") (name "Net-(LCD1-V0)") (class "Default")
      (node (ref "C50") (pin "1") (pinfunction "1_1") (pintype "passive"))
      (node (ref "LCD1") (pin "21") (pinfunction "V0_21") (pintype "bidirectional"))
    )
    (net (code "124") (name "Net-(LCD1-V1)") (class "Default")
      (node (ref "C55") (pin "1") (pinfunction "1_1") (pintype "passive"))
      (node (ref "LCD1") (pin "22") (pinfunction "V1_22") (pintype "bidirectional"))
    )
    (net (code "125") (name "Net-(LCD1-V2)") (class "Default")
      (node (ref "C51") (pin "1") (pinfunction "1_1") (pintype "passive"))
      (node (ref "LCD1") (pin "23") (pinfunction "V2_23") (pintype "bidirectional"))
    )
    (net (code "126") (name "Net-(LCD1-V3)") (class "Default")
      (node (ref "C56") (pin "1") (pinfunction "1_1") (pintype "passive"))
      (node (ref "LCD1") (pin "24") (pinfunction "V3_24") (pintype "input"))
    )
    (net (code "127") (name "Net-(LCD1-V4)") (class "Default")
      (node (ref "C52") (pin "1") (pinfunction "1_1") (pintype "passive"))
      (node (ref "LCD1") (pin "25") (pinfunction "V4_25") (pintype "output"))
    )
    (net (code "128") (name "Net-(R1-1)") (class "Default")
      (node (ref "C1") (pin "2") (pinfunction "2_2") (pintype "passive"))
      (node (ref "IC1") (pin "2") (pinfunction "IN_2") (pintype "input"))
      (node (ref "IC1") (pin "2@1") (pinfunction "IN_2@1") (pintype "input"))
      (node (ref "R1") (pin "P$1") (pinfunction "1_P$1") (pintype "passive"))
    )
    (net (code "129") (name "Net-(R3-1)") (class "Default")
      (node (ref "C2") (pin "2") (pinfunction "2_2") (pintype "passive"))
      (node (ref "IC2") (pin "2") (pinfunction "IN_2") (pintype "input"))
      (node (ref "IC2") (pin "2@1") (pinfunction "IN_2@1") (pintype "input"))
      (node (ref "R3") (pin "P$1") (pinfunction "1_P$1") (pintype "passive"))
    )
    (net (code "130") (name "Net-(R6-1)") (class "Default")
      (node (ref "C4") (pin "1") (pinfunction "1_1") (pintype "passive"))
      (node (ref "R6") (pin "P$1") (pinfunction "1_P$1") (pintype "passive"))
    )
    (net (code "131") (name "Net-(R7-1)") (class "Default")
      (node (ref "C5") (pin "1") (pinfunction "1_1") (pintype "passive"))
      (node (ref "R7") (pin "P$1") (pinfunction "1_P$1") (pintype "passive"))
    )
    (net (code "132") (name "Net-(R13-1)") (class "Default")
      (node (ref "C12") (pin "1") (pinfunction "1_1") (pintype "passive"))
      (node (ref "D2") (pin "C") (pinfunction "C_C") (pintype "passive"))
      (node (ref "R13") (pin "P$1") (pinfunction "1_P$1") (pintype "passive"))
      (node (ref "R19") (pin "P$2") (pinfunction "2_P$2") (pintype "passive"))
    )
    (net (code "133") (name "Net-(R14-2)") (class "Default")
      (node (ref "R14") (pin "P$2") (pinfunction "2_P$2") (pintype "passive"))
      (node (ref "R18") (pin "P$1") (pinfunction "1_P$1") (pintype "passive"))
    )
    (net (code "134") (name "Net-(R15-2)") (class "Default")
      (node (ref "C13") (pin "2") (pinfunction "2_2") (pintype "passive"))
      (node (ref "D1") (pin "A") (pinfunction "A_A") (pintype "passive"))
      (node (ref "R15") (pin "P$2") (pinfunction "2_P$2") (pintype "passive"))
      (node (ref "R20") (pin "P$2") (pinfunction "2_P$2") (pintype "passive"))
    )
    (net (code "135") (name "Net-(R16-1)") (class "Default")
      (node (ref "R16") (pin "P$1") (pinfunction "1_P$1") (pintype "passive"))
      (node (ref "R17") (pin "P$2") (pinfunction "2_P$2") (pintype "passive"))
    )
    (net (code "136") (name "Net-(R22-2)") (class "Default")
      (node (ref "R22") (pin "P$2") (pinfunction "2_P$2") (pintype "passive"))
      (node (ref "R23") (pin "P$1") (pinfunction "1_P$1") (pintype "passive"))
    )
    (net (code "137") (name "Net-(R24-2)") (class "Default")
      (node (ref "R24") (pin "P$2") (pinfunction "2_P$2") (pintype "passive"))
      (node (ref "R28") (pin "P$1") (pinfunction "1_P$1") (pintype "passive"))
    )
    (net (code "138") (name "Net-(R26-2)") (class "Default")
      (node (ref "R26") (pin "P$2") (pinfunction "2_P$2") (pintype "passive"))
      (node (ref "R29") (pin "P$1") (pinfunction "1_P$1") (pintype "passive"))
    )
    (net (code "139") (name "Net-(R30-1)") (class "Default")
      (node (ref "R30") (pin "P$1") (pinfunction "1_P$1") (pintype "passive"))
      (node (ref "R31") (pin "P$2") (pinfunction "2_P$2") (pintype "passive"))
      (node (ref "T1") (pin "1") (pinfunction "B_1") (pintype "passive"))
    )
    (net (code "140") (name "Net-(R32-1)") (class "Default")
      (node (ref "D3") (pin "K") (pinfunction "K_K") (pintype "output"))
      (node (ref "R32") (pin "P$1") (pinfunction "1_P$1") (pintype "passive"))
      (node (ref "T1") (pin "3") (pinfunction "C_3") (pintype "passive"))
    )
    (net (code "141") (name "Net-(R34-2)") (class "Default")
      (node (ref "D3") (pin "A") (pinfunction "A_A") (pintype "input"))
      (node (ref "R34") (pin "P$2") (pinfunction "2_P$2") (pintype "passive"))
    )
    (net (code "142") (name "Net-(R47-1)") (class "Default")
      (node (ref "R47") (pin "P$1") (pinfunction "1_P$1") (pintype "passive"))
      (node (ref "R48") (pin "P$2") (pinfunction "2_P$2") (pintype "passive"))
      (node (ref "R49") (pin "P$2") (pinfunction "2_P$2") (pintype "passive"))
    )
    (net (code "143") (name "Net-(R62-1)") (class "Default")
      (node (ref "R62") (pin "P$1") (pinfunction "1_P$1") (pintype "passive"))
      (node (ref "T2") (pin "1") (pinfunction "B_1") (pintype "passive"))
    )
    (net (code "144") (name "Net-(R78-1)") (class "Default")
      (node (ref "R78") (pin "P$1") (pinfunction "1_P$1") (pintype "passive"))
      (node (ref "T3") (pin "1") (pinfunction "B_1") (pintype "passive"))
    )
    (net (code "145") (name "Net-(RN1-R1A)") (class "Default")
      (node (ref "RN1") (pin "1") (pinfunction "R1A_1") (pintype "bidirectional"))
      (node (ref "RN1") (pin "4") (pinfunction "R4A_4") (pintype "bidirectional"))
    )
    (net (code "146") (name "Net-(RN1-R2A)") (class "Default")
      (node (ref "RN1") (pin "2") (pinfunction "R2A_2") (pintype "bidirectional"))
      (node (ref "RN1") (pin "3") (pinfunction "R3A_3") (pintype "bidirectional"))
    )
    (net (code "147") (name "Net-(RN2-R1A)") (class "Default")
      (node (ref "RN2") (pin "1") (pinfunction "R1A_1") (pintype "bidirectional"))
      (node (ref "RN2") (pin "2") (pinfunction "R2A_2") (pintype "bidirectional"))
    )
    (net (code "148") (name "PWR_A_EN") (class "Default")
      (node (ref "IC20") (pin "33") (pinfunction "PA12_33") (pintype "bidirectional"))
      (node (ref "R8") (pin "P$2") (pinfunction "2_P$2") (pintype "passive"))
    )
    (net (code "149") (name "PWR_D_EN") (class "Default")
      (node (ref "IC20") (pin "32") (pinfunction "PA11_32") (pintype "bidirectional"))
      (node (ref "R12") (pin "P$1") (pinfunction "1_P$1") (pintype "passive"))
    )
    (net (code "150") (name "SW_VRH") (class "Default")
      (node (ref "IC8") (pin "6") (pinfunction "IN_6") (pintype "input"))
    )
    (net (code "151") (name "VDD") (class "Default")
      (node (ref "C40") (pin "1") (pinfunction "1_1") (pintype "passive"))
      (node (ref "C43") (pin "1") (pinfunction "1_1") (pintype "passive"))
      (node (ref "C44") (pin "1") (pinfunction "1_1") (pintype "passive"))
      (node (ref "C46") (pin "1") (pinfunction "1_1") (pintype "passive"))
      (node (ref "C47") (pin "1") (pinfunction "1_1") (pintype "passive"))
      (node (ref "C8") (pin "2") (pinfunction "2_2") (pintype "passive"))
      (node (ref "IC19") (pin "3") (pinfunction "~{WP}_3") (pintype "input"))
      (node (ref "IC19") (pin "7") (pinfunction "~{HOLD}_7") (pintype "input"))
      (node (ref "IC19") (pin "8") (pinfunction "VDD_8") (pintype "power_in"))
      (node (ref "IC2") (pin "3") (pinfunction "OUT_3") (pintype "output"))
      (node (ref "IC20") (pin "24") (pinfunction "VDD_1_24") (pintype "bidirectional"))
      (node (ref "IC20") (pin "36") (pinfunction "VDD_2_36") (pintype "bidirectional"))
      (node (ref "IC20") (pin "48") (pinfunction "VDD_3_48") (pintype "bidirectional"))
      (node (ref "IC20") (pin "9") (pinfunction "VDDA_9") (pintype "bidirectional"))
      (node (ref "IC21") (pin "5") (pinfunction "VDD_5") (pintype "power_in"))
      (node (ref "JP3") (pin "7") (pinfunction "7_7") (pintype "passive"))
      (node (ref "JP4") (pin "3") (pinfunction "3_3") (pintype "passive"))
      (node (ref "LCD1") (pin "34") (pinfunction "VDD2_34") (pintype "power_in"))
      (node (ref "LCD1") (pin "35") (pinfunction "VDD_35") (pintype "power_in"))
      (node (ref "R66") (pin "P$1") (pinfunction "1_P$1") (pintype "passive"))
      (node (ref "R68") (pin "P$2") (pinfunction "2_P$2") (pintype "passive"))
      (node (ref "R69") (pin "P$2") (pinfunction "2_P$2") (pintype "passive"))
      (node (ref "R70") (pin "P$2") (pinfunction "2_P$2") (pintype "passive"))
      (node (ref "R71") (pin "P$2") (pinfunction "2_P$2") (pintype "passive"))
      (node (ref "R72") (pin "P$2") (pinfunction "2_P$2") (pintype "passive"))
      (node (ref "R75") (pin "P$2") (pinfunction "2_P$2") (pintype "passive"))
      (node (ref "R76") (pin "P$2") (pinfunction "2_P$2") (pintype "passive"))
    )
    (net (code "152") (name "VR_-7V") (class "Default")
      (node (ref "IC10") (pin "2") (pinfunction "-IN_2") (pintype "input"))
      (node (ref "IC10") (pin "6") (pinfunction "OUT_6") (pintype "output"))
      (node (ref "IC8") (pin "8") (pinfunction "S2_8") (pintype "bidirectional"))
      (node (ref "JP2") (pin "1") (pinfunction "1_1") (pintype "passive"))
      (node (ref "RN1") (pin "5") (pinfunction "R4B_5") (pintype "bidirectional"))
      (node (ref "TP21") (pin "P$1") (pinfunction "P$1_P$1") (pintype "bidirectional"))
    )
    (net (code "153") (name "VR_-7V_UB") (class "Default")
      (node (ref "C24") (pin "1") (pinfunction "1_1") (pintype "passive"))
      (node (ref "IC10") (pin "3") (pinfunction "+IN_3") (pintype "input"))
      (node (ref "R34") (pin "P$1") (pinfunction "1_P$1") (pintype "passive"))
      (node (ref "R37") (pin "P$2") (pinfunction "2_P$2") (pintype "passive"))
    )
    (net (code "154") (name "VR_-10V") (class "Default")
      (node (ref "IC15") (pin "6") (pinfunction "OUT_6") (pintype "output"))
      (node (ref "R41") (pin "P$1") (pinfunction "1_P$1") (pintype "passive"))
      (node (ref "R42") (pin "P$1") (pinfunction "1_P$1") (pintype "passive"))
    )
    (net (code "155") (name "unconnected-(IC3-SEQ-Pad5)") (class "Default")
      (node (ref "IC3") (pin "5") (pinfunction "SEQ_5") (pintype "bidirectional"))
    )
    (net (code "156") (name "unconnected-(IC3-SLEW-Pad6)") (class "Default")
      (node (ref "IC3") (pin "6") (pinfunction "SLEW_6") (pintype "bidirectional"))
    )
    (net (code "157") (name "unconnected-(IC3-SS-Pad10)") (class "Default")
      (node (ref "IC3") (pin "10") (pinfunction "SS_10") (pintype "bidirectional"))
    )
    (net (code "158") (name "unconnected-(IC4-BYP-Pad4)") (class "Default")
      (node (ref "IC4") (pin "4") (pinfunction "BYP_4") (pintype "bidirectional"))
    )
    (net (code "159") (name "unconnected-(IC10-ON1-Pad1)") (class "Default")
      (node (ref "IC10") (pin "1") (pinfunction "ON1_1") (pintype "passive"))
    )
    (net (code "160") (name "unconnected-(IC10-ON2-Pad5)") (class "Default")
      (node (ref "IC10") (pin "5") (pinfunction "ON2_5") (pintype "passive"))
    )
    (net (code "161") (name "unconnected-(IC10-OPT-Pad8)") (class "Default")
      (node (ref "IC10") (pin "8") (pinfunction "OPT_8") (pintype "passive"))
    )
    (net (code "162") (name "unconnected-(IC12-ON1-Pad1)") (class "Default")
      (node (ref "IC12") (pin "1") (pinfunction "ON1_1") (pintype "passive"))
    )
    (net (code "163") (name "unconnected-(IC12-ON2-Pad5)") (class "Default")
      (node (ref "IC12") (pin "5") (pinfunction "ON2_5") (pintype "passive"))
    )
    (net (code "164") (name "unconnected-(IC12-OPT-Pad8)") (class "Default")
      (node (ref "IC12") (pin "8") (pinfunction "OPT_8") (pintype "passive"))
    )
    (net (code "165") (name "unconnected-(IC14-ON2-Pad5)") (class "Default")
      (node (ref "IC14") (pin "5") (pinfunction "ON2_5") (pintype "passive"))
    )
    (net (code "166") (name "unconnected-(IC15-ON1-Pad1)") (class "Default")
      (node (ref "IC15") (pin "1") (pinfunction "ON1_1") (pintype "passive"))
    )
    (net (code "167") (name "unconnected-(IC15-ON2-Pad5)") (class "Default")
      (node (ref "IC15") (pin "5") (pinfunction "ON2_5") (pintype "passive"))
    )
    (net (code "168") (name "unconnected-(IC15-OPT-Pad8)") (class "Default")
      (node (ref "IC15") (pin "8") (pinfunction "OPT_8") (pintype "passive"))
    )
    (net (code "169") (name "unconnected-(IC16-ON{slash}STR-Pad6)") (class "Default")
      (node (ref "IC16") (pin "6") (pinfunction "ON/STR_6") (pintype "passive"))
    )
    (net (code "170") (name "unconnected-(IC18-PB4C-Pad27)") (class "Default")
      (node (ref "IC18") (pin "27") (pinfunction "PB4C_27") (pintype "bidirectional"))
    )
    (net (code "171") (name "unconnected-(IC18-PB4D-Pad28)") (class "Default")
      (node (ref "IC18") (pin "28") (pinfunction "PB4D_28") (pintype "bidirectional"))
    )
    (net (code "172") (name "unconnected-(IC18-PB6A-Pad29)") (class "Default")
      (node (ref "IC18") (pin "29") (pinfunction "PB6A_29") (pintype "bidirectional"))
    )
    (net (code "173") (name "unconnected-(IC18-PB6B-Pad30)") (class "Default")
      (node (ref "IC18") (pin "30") (pinfunction "PB6B_30") (pintype "bidirectional"))
    )
    (net (code "174") (name "unconnected-(IC18-PB6C-Pad31)") (class "Default")
      (node (ref "IC18") (pin "31") (pinfunction "PB6C_31") (pintype "bidirectional"))
    )
    (net (code "175") (name "unconnected-(IC18-PB6D-Pad32)") (class "Default")
      (node (ref "IC18") (pin "32") (pinfunction "PB6D_32") (pintype "bidirectional"))
    )
    (net (code "176") (name "unconnected-(IC18-PB9A-Pad34)") (class "Default")
      (node (ref "IC18") (pin "34") (pinfunction "PB9A_34") (pintype "bidirectional"))
    )
    (net (code "177") (name "unconnected-(IC18-PB11B-Pad39)") (class "Default")
      (node (ref "IC18") (pin "39") (pinfunction "PB11B_39") (pintype "bidirectional"))
    )
    (net (code "178") (name "unconnected-(IC18-PB15A-Pad40)") (class "Default")
      (node (ref "IC18") (pin "40") (pinfunction "PB15A_40") (pintype "bidirectional"))
    )
    (net (code "179") (name "unconnected-(IC18-PB15B-Pad41)") (class "Default")
      (node (ref "IC18") (pin "41") (pinfunction "PB15B_41") (pintype "bidirectional"))
    )
    (net (code "180") (name "unconnected-(IC18-PB18A-Pad42)") (class "Default")
      (node (ref "IC18") (pin "42") (pinfunction "PB18A_42") (pintype "bidirectional"))
    )
    (net (code "181") (name "unconnected-(IC18-PB18B-Pad43)") (class "Default")
      (node (ref "IC18") (pin "43") (pinfunction "PB18B_43") (pintype "bidirectional"))
    )
    (net (code "182") (name "unconnected-(IC18-PB18C-Pad45)") (class "Default")
      (node (ref "IC18") (pin "45") (pinfunction "PB18C_45") (pintype "bidirectional"))
    )
    (net (code "183") (name "unconnected-(IC18-PB18D-Pad47)") (class "Default")
      (node (ref "IC18") (pin "47") (pinfunction "PB18D_47") (pintype "bidirectional"))
    )
    (net (code "184") (name "unconnected-(IC18-PB20C-Pad48)") (class "Default")
      (node (ref "IC18") (pin "48") (pinfunction "PB20C_48") (pintype "bidirectional"))
    )
    (net (code "185") (name "unconnected-(IC18-PB20D-Pad49)") (class "Default")
      (node (ref "IC18") (pin "49") (pinfunction "PB20D_49") (pintype "bidirectional"))
    )
    (net (code "186") (name "unconnected-(IC18-PL2C-Pad1)") (class "Default")
      (node (ref "IC18") (pin "1") (pinfunction "PL2C_1") (pintype "bidirectional"))
    )
    (net (code "187") (name "unconnected-(IC18-PL2D-Pad2)") (class "Default")
      (node (ref "IC18") (pin "2") (pinfunction "PL2D_2") (pintype "bidirectional"))
    )
    (net (code "188") (name "unconnected-(IC18-PL3B-Pad4)") (class "Default")
      (node (ref "IC18") (pin "4") (pinfunction "PL3B_4") (pintype "bidirectional"))
    )
    (net (code "189") (name "unconnected-(IC18-PL3C-Pad7)") (class "Default")
      (node (ref "IC18") (pin "7") (pinfunction "PL3C_7") (pintype "bidirectional"))
    )
    (net (code "190") (name "unconnected-(IC18-PL3D-Pad8)") (class "Default")
      (node (ref "IC18") (pin "8") (pinfunction "PL3D_8") (pintype "bidirectional"))
    )
    (net (code "191") (name "unconnected-(IC18-PL4A-Pad9)") (class "Default")
      (node (ref "IC18") (pin "9") (pinfunction "PL4A_9") (pintype "bidirectional"))
    )
    (net (code "192") (name "unconnected-(IC18-PL4B-Pad10)") (class "Default")
      (node (ref "IC18") (pin "10") (pinfunction "PL4B_10") (pintype "bidirectional"))
    )
    (net (code "193") (name "unconnected-(IC18-PL8A-Pad16)") (class "Default")
      (node (ref "IC18") (pin "16") (pinfunction "PL8A_16") (pintype "bidirectional"))
    )
    (net (code "194") (name "unconnected-(IC18-PL8B-Pad17)") (class "Default")
      (node (ref "IC18") (pin "17") (pinfunction "PL8B_17") (pintype "bidirectional"))
    )
    (net (code "195") (name "unconnected-(IC18-PL8D-Pad19)") (class "Default")
      (node (ref "IC18") (pin "19") (pinfunction "PL8D_19") (pintype "bidirectional"))
    )
    (net (code "196") (name "unconnected-(IC18-PL9A-Pad20)") (class "Default")
      (node (ref "IC18") (pin "20") (pinfunction "PL9A_20") (pintype "bidirectional"))
    )
    (net (code "197") (name "unconnected-(IC18-PL9B-Pad21)") (class "Default")
      (node (ref "IC18") (pin "21") (pinfunction "PL9B_21") (pintype "bidirectional"))
    )
    (net (code "198") (name "unconnected-(IC18-PL10C-Pad24)") (class "Default")
      (node (ref "IC18") (pin "24") (pinfunction "PL10C_24") (pintype "bidirectional"))
    )
    (net (code "199") (name "unconnected-(IC18-PL10D-Pad25)") (class "Default")
      (node (ref "IC18") (pin "25") (pinfunction "PL10D_25") (pintype "bidirectional"))
    )
    (net (code "200") (name "unconnected-(IC18-PR2A-Pad75)") (class "Default")
      (node (ref "IC18") (pin "75") (pinfunction "PR2A_75") (pintype "bidirectional"))
    )
    (net (code "201") (name "unconnected-(IC18-PR2B-Pad74)") (class "Default")
      (node (ref "IC18") (pin "74") (pinfunction "PR2B_74") (pintype "bidirectional"))
    )
    (net (code "202") (name "unconnected-(IC18-PR3A-Pad71)") (class "Default")
      (node (ref "IC18") (pin "71") (pinfunction "PR3A_71") (pintype "bidirectional"))
    )
    (net (code "203") (name "unconnected-(IC18-PR3B-Pad70)") (class "Default")
      (node (ref "IC18") (pin "70") (pinfunction "PR3B_70") (pintype "bidirectional"))
    )
    (net (code "204") (name "unconnected-(IC18-PR4A-Pad69)") (class "Default")
      (node (ref "IC18") (pin "69") (pinfunction "PR4A_69") (pintype "bidirectional"))
    )
    (net (code "205") (name "unconnected-(IC18-PR4B-Pad68)") (class "Default")
      (node (ref "IC18") (pin "68") (pinfunction "PR4B_68") (pintype "bidirectional"))
    )
    (net (code "206") (name "unconnected-(IC18-PR4C-Pad67)") (class "Default")
      (node (ref "IC18") (pin "67") (pinfunction "PR4C_67") (pintype "bidirectional"))
    )
    (net (code "207") (name "unconnected-(IC18-PR4D-Pad66)") (class "Default")
      (node (ref "IC18") (pin "66") (pinfunction "PR4D_66") (pintype "bidirectional"))
    )
    (net (code "208") (name "unconnected-(IC18-PR5A-Pad65)") (class "Default")
      (node (ref "IC18") (pin "65") (pinfunction "PR5A_65") (pintype "bidirectional"))
    )
    (net (code "209") (name "unconnected-(IC18-PR5B-Pad64)") (class "Default")
      (node (ref "IC18") (pin "64") (pinfunction "PR5B_64") (pintype "bidirectional"))
    )
    (net (code "210") (name "unconnected-(IC18-PR5D-Pad62)") (class "Default")
      (node (ref "IC18") (pin "62") (pinfunction "PR5D_62") (pintype "bidirectional"))
    )
    (net (code "211") (name "unconnected-(IC18-PR8A-Pad61)") (class "Default")
      (node (ref "IC18") (pin "61") (pinfunction "PR8A_61") (pintype "bidirectional"))
    )
    (net (code "212") (name "unconnected-(IC18-PR8C-Pad60)") (class "Default")
      (node (ref "IC18") (pin "60") (pinfunction "PR8C_60") (pintype "bidirectional"))
    )
    (net (code "213") (name "unconnected-(IC18-PR8D-Pad59)") (class "Default")
      (node (ref "IC18") (pin "59") (pinfunction "PR8D_59") (pintype "bidirectional"))
    )
    (net (code "214") (name "unconnected-(IC18-PR9A-Pad58)") (class "Default")
      (node (ref "IC18") (pin "58") (pinfunction "PR9A_58") (pintype "bidirectional"))
    )
    (net (code "215") (name "unconnected-(IC18-PR9B-Pad57)") (class "Default")
      (node (ref "IC18") (pin "57") (pinfunction "PR9B_57") (pintype "bidirectional"))
    )
    (net (code "216") (name "unconnected-(IC18-PR9C-Pad54)") (class "Default")
      (node (ref "IC18") (pin "54") (pinfunction "PR9C_54") (pintype "bidirectional"))
    )
    (net (code "217") (name "unconnected-(IC18-PR9D-Pad53)") (class "Default")
      (node (ref "IC18") (pin "53") (pinfunction "PR9D_53") (pintype "bidirectional"))
    )
    (net (code "218") (name "unconnected-(IC18-PR10C-Pad52)") (class "Default")
      (node (ref "IC18") (pin "52") (pinfunction "PR10C_52") (pintype "bidirectional"))
    )
    (net (code "219") (name "unconnected-(IC18-PR10D-Pad51)") (class "Default")
      (node (ref "IC18") (pin "51") (pinfunction "PR10D_51") (pintype "bidirectional"))
    )
    (net (code "220") (name "unconnected-(IC18-PT9A-Pad99)") (class "Default")
      (node (ref "IC18") (pin "99") (pinfunction "PT9A_99") (pintype "bidirectional"))
    )
    (net (code "221") (name "unconnected-(IC18-PT9B-Pad98)") (class "Default")
      (node (ref "IC18") (pin "98") (pinfunction "PT9B_98") (pintype "bidirectional"))
    )
    (net (code "222") (name "unconnected-(IC18-PT10A-Pad97)") (class "Default")
      (node (ref "IC18") (pin "97") (pinfunction "PT10A_97") (pintype "bidirectional"))
    )
    (net (code "223") (name "unconnected-(IC18-PT10B-Pad96)") (class "Default")
      (node (ref "IC18") (pin "96") (pinfunction "PT10B_96") (pintype "bidirectional"))
    )
    (net (code "224") (name "unconnected-(IC18-PT12A-Pad88)") (class "Default")
      (node (ref "IC18") (pin "88") (pinfunction "PT12A_88") (pintype "bidirectional"))
    )
    (net (code "225") (name "unconnected-(IC18-PT12B-Pad87)") (class "Default")
      (node (ref "IC18") (pin "87") (pinfunction "PT12B_87") (pintype "bidirectional"))
    )
    (net (code "226") (name "unconnected-(IC18-PT12C-Pad86)") (class "Default")
      (node (ref "IC18") (pin "86") (pinfunction "PT12C_86") (pintype "bidirectional"))
    )
    (net (code "227") (name "unconnected-(IC18-PT15C{slash}JTAGENB-Pad82)") (class "Default")
      (node (ref "IC18") (pin "82") (pinfunction "PT15C/JTAGENB_82") (pintype "bidirectional"))
    )
    (net (code "228") (name "unconnected-(IC18-PT15D-Pad81)") (class "Default")
      (node (ref "IC18") (pin "81") (pinfunction "PT15D_81") (pintype "bidirectional"))
    )
    (net (code "229") (name "unconnected-(IC18-PT16C-Pad78)") (class "Default")
      (node (ref "IC18") (pin "78") (pinfunction "PT16C_78") (pintype "bidirectional"))
    )
    (net (code "230") (name "unconnected-(IC18-PT17C{slash}INITN-Pad77)") (class "Default")
      (node (ref "IC18") (pin "77") (pinfunction "PT17C/INITN_77") (pintype "bidirectional"))
    )
    (net (code "231") (name "unconnected-(IC18-PT17D{slash}DONE-Pad76)") (class "Default")
      (node (ref "IC18") (pin "76") (pinfunction "PT17D/DONE_76") (pintype "bidirectional"))
    )
    (net (code "232") (name "unconnected-(IC20-PB7-Pad43)") (class "Default")
      (node (ref "IC20") (pin "43") (pinfunction "PB7_43") (pintype "bidirectional"))
    )
    (net (code "233") (name "unconnected-(IC20-PC13-WKUP2-Pad2)") (class "Default")
      (node (ref "IC20") (pin "2") (pinfunction "PC13-WKUP2_2") (pintype "bidirectional"))
    )
    (net (code "234") (name "unconnected-(IC20-PC14-OSC32_IN-Pad3)") (class "Default")
      (node (ref "IC20") (pin "3") (pinfunction "PC14-OSC32_IN_3") (pintype "bidirectional"))
    )
    (net (code "235") (name "unconnected-(IC20-PC15-OSC32_OUT-Pad4)") (class "Default")
      (node (ref "IC20") (pin "4") (pinfunction "PC15-OSC32_OUT_4") (pintype "bidirectional"))
    )
    (net (code "236") (name "unconnected-(IC20-VLCD-Pad1)") (class "Default")
      (node (ref "IC20") (pin "1") (pinfunction "VLCD_1") (pintype "bidirectional"))
    )
  )
)
